# reflex_brainboard_RevG.net
KiCad netlist of a schematic drawn in Altium Designer
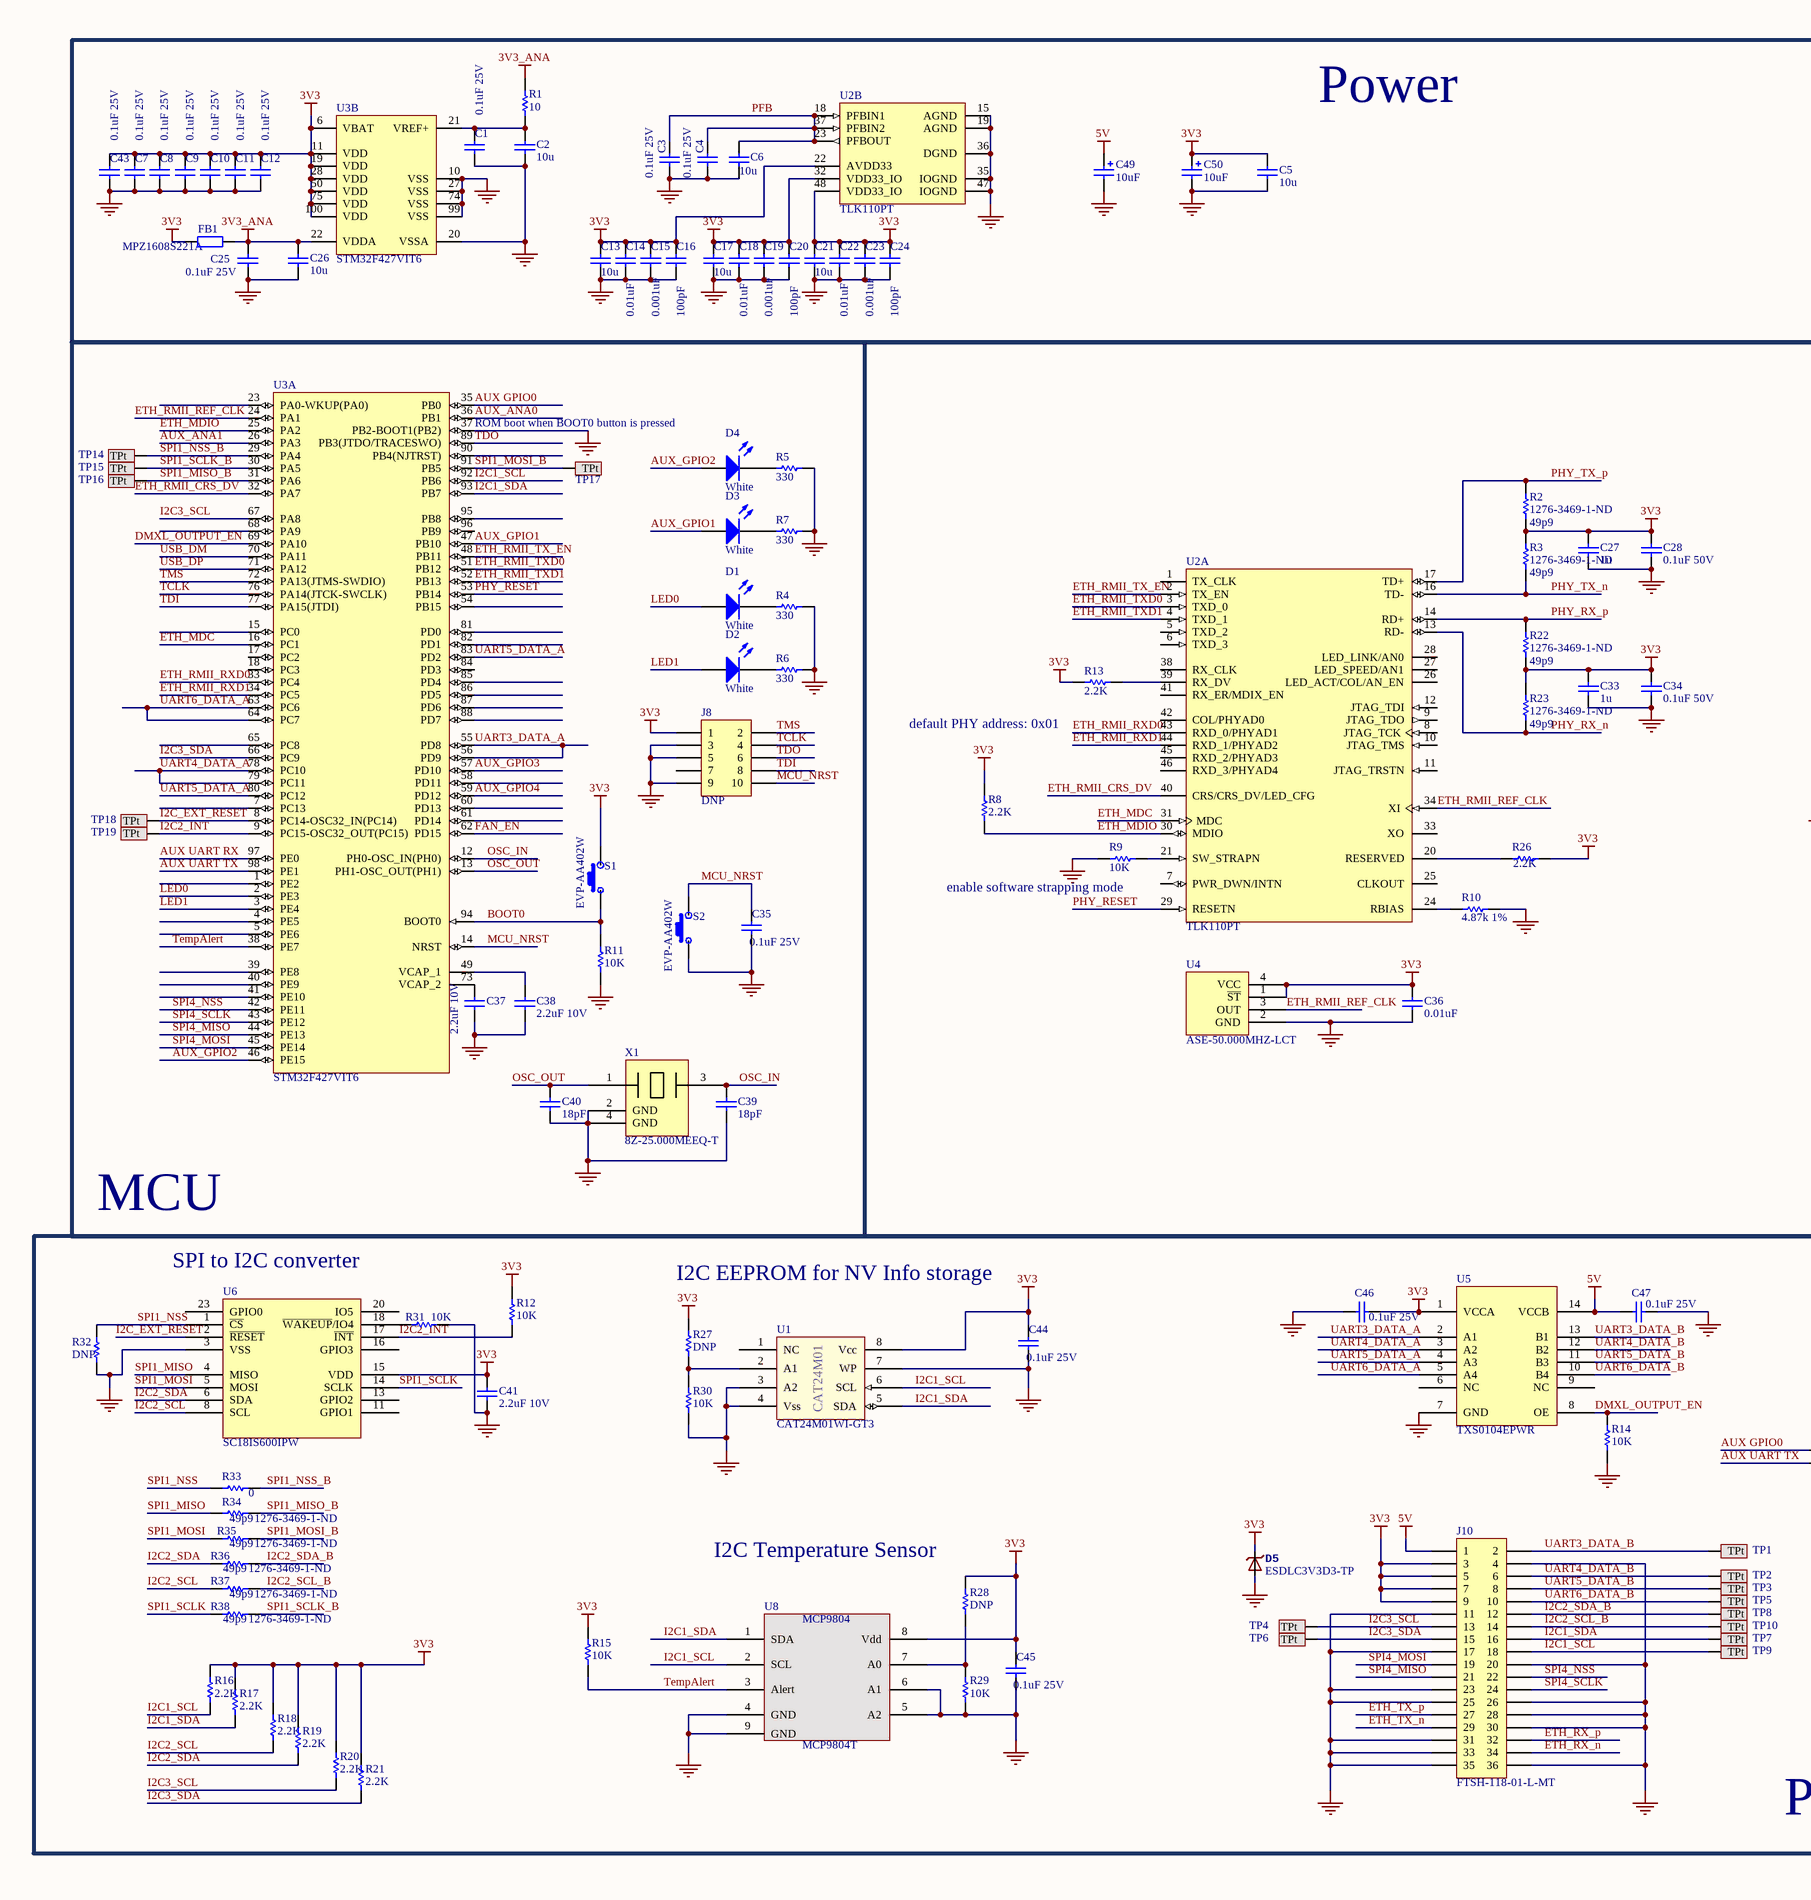
[diagram p0: reflex_brainboard_RevG.SchDoc, left]
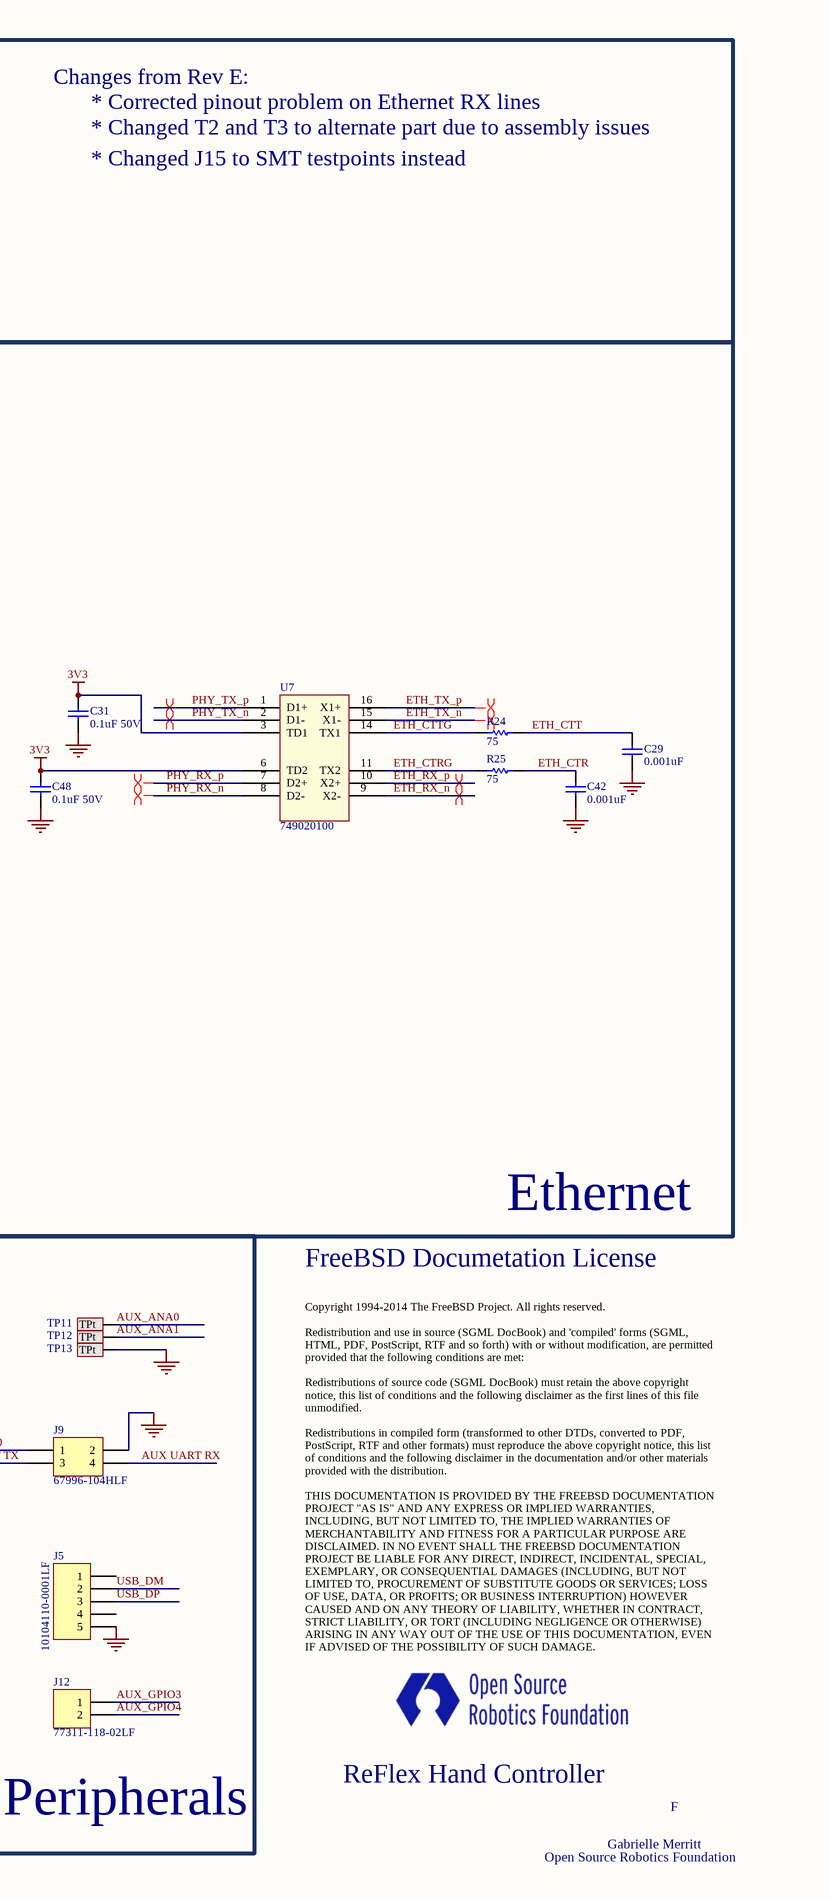
[diagram p1: reflex_brainboard_RevG.SchDoc, right]

(export (version "E")
  (design (tool "Eeschema 10.0.6"))
  (components
    (comp (ref "C1")
      (value "0.1uF 25V")
      (footprint "Generic_0603")
      (description "Capacitor 0.1uF 0603 package")
      (libsource (lib "RHR") (part "Cap_0603_0.1uF_25V"))
    )
    (comp (ref "C2")
      (value "10u")
      (footprint "GENERIC_0603")
      (description "Capacitor")
      (fields
        (field (name "MANUFACTURER") "TDK Corporation")
        (field (name "MANUFACTURER PART NUMBER") "C1608X5R1E106M080AC")
      )
      (libsource (lib "RHR") (part "Cap_0603_10uF"))
    )
    (comp (ref "C3")
      (value "0.1uF 25V")
      (footprint "Generic_0603")
      (description "Capacitor 0.1uF 0603 package")
      (libsource (lib "RHR") (part "Cap_0603_0.1uF_25V"))
    )
    (comp (ref "C4")
      (value "0.1uF 25V")
      (footprint "Generic_0603")
      (description "Capacitor 0.1uF 0603 package")
      (libsource (lib "RHR") (part "Cap_0603_0.1uF_25V"))
    )
    (comp (ref "C5")
      (value "10u")
      (footprint "GENERIC_0603")
      (description "Capacitor")
      (fields
        (field (name "MANUFACTURER") "TDK Corporation")
        (field (name "MANUFACTURER PART NUMBER") "C1608X5R1E106M080AC")
      )
      (libsource (lib "RHR") (part "Cap_0603_10uF"))
    )
    (comp (ref "C6")
      (value "10u")
      (footprint "GENERIC_0603")
      (description "Capacitor")
      (fields
        (field (name "MANUFACTURER") "TDK Corporation")
        (field (name "MANUFACTURER PART NUMBER") "C1608X5R1E106M080AC")
      )
      (libsource (lib "RHR") (part "Cap_0603_10uF"))
    )
    (comp (ref "C7")
      (value "0.1uF 25V")
      (footprint "Generic_0603")
      (description "Capacitor 0.1uF 0603 package")
      (libsource (lib "RHR") (part "Cap_0603_0.1uF_25V"))
    )
    (comp (ref "C8")
      (value "0.1uF 25V")
      (footprint "Generic_0603")
      (description "Capacitor 0.1uF 0603 package")
      (libsource (lib "RHR") (part "Cap_0603_0.1uF_25V"))
    )
    (comp (ref "C9")
      (value "0.1uF 25V")
      (footprint "Generic_0603")
      (description "Capacitor 0.1uF 0603 package")
      (libsource (lib "RHR") (part "Cap_0603_0.1uF_25V"))
    )
    (comp (ref "C10")
      (value "0.1uF 25V")
      (footprint "Generic_0603")
      (description "Capacitor 0.1uF 0603 package")
      (libsource (lib "RHR") (part "Cap_0603_0.1uF_25V"))
    )
    (comp (ref "C11")
      (value "0.1uF 25V")
      (footprint "Generic_0603")
      (description "Capacitor 0.1uF 0603 package")
      (libsource (lib "RHR") (part "Cap_0603_0.1uF_25V"))
    )
    (comp (ref "C12")
      (value "0.1uF 25V")
      (footprint "Generic_0603")
      (description "Capacitor 0.1uF 0603 package")
      (libsource (lib "RHR") (part "Cap_0603_0.1uF_25V"))
    )
    (comp (ref "C13")
      (value "10u")
      (footprint "GENERIC_0603")
      (description "Capacitor")
      (fields
        (field (name "MANUFACTURER") "TDK Corporation")
        (field (name "MANUFACTURER PART NUMBER") "C1608X5R1E106M080AC")
      )
      (libsource (lib "RHR") (part "Cap_0603_10uF"))
    )
    (comp (ref "C14")
      (value "0.01uF")
      (footprint "Generic_0402")
      (description "Capacitor 0.01uF 0402 package")
      (libsource (lib "RHR") (part "Cap_0402_0p01uF"))
    )
    (comp (ref "C15")
      (value "0.001uF")
      (footprint "Generic_0402")
      (description "Capacitor 0.001uF 0402 package")
      (libsource (lib "RHR") (part "Cap_0402_0p001uF"))
    )
    (comp (ref "C16")
      (value "100pF")
      (footprint "Generic_0402")
      (description "Capacitor 100pF 0402 package")
      (libsource (lib "RHR") (part "Cap_0402_100pF"))
    )
    (comp (ref "C17")
      (value "10u")
      (footprint "GENERIC_0603")
      (description "Capacitor")
      (fields
        (field (name "MANUFACTURER") "TDK Corporation")
        (field (name "MANUFACTURER PART NUMBER") "C1608X5R1E106M080AC")
      )
      (libsource (lib "RHR") (part "Cap_0603_10uF"))
    )
    (comp (ref "C18")
      (value "0.01uF")
      (footprint "Generic_0402")
      (description "Capacitor 0.01uF 0402 package")
      (libsource (lib "RHR") (part "Cap_0402_0p01uF"))
    )
    (comp (ref "C19")
      (value "0.001uF")
      (footprint "Generic_0402")
      (description "Capacitor 0.001uF 0402 package")
      (libsource (lib "RHR") (part "Cap_0402_0p001uF"))
    )
    (comp (ref "C20")
      (value "100pF")
      (footprint "Generic_0402")
      (description "Capacitor 100pF 0402 package")
      (libsource (lib "RHR") (part "Cap_0402_100pF"))
    )
    (comp (ref "C21")
      (value "10u")
      (footprint "GENERIC_0603")
      (description "Capacitor")
      (fields
        (field (name "MANUFACTURER") "TDK Corporation")
        (field (name "MANUFACTURER PART NUMBER") "C1608X5R1E106M080AC")
      )
      (libsource (lib "RHR") (part "Cap_0603_10uF"))
    )
    (comp (ref "C22")
      (value "0.01uF")
      (footprint "Generic_0402")
      (description "Capacitor 0.01uF 0402 package")
      (libsource (lib "RHR") (part "Cap_0402_0p01uF"))
    )
    (comp (ref "C23")
      (value "0.001uF")
      (footprint "Generic_0402")
      (description "Capacitor 0.001uF 0402 package")
      (libsource (lib "RHR") (part "Cap_0402_0p001uF"))
    )
    (comp (ref "C24")
      (value "100pF")
      (footprint "Generic_0402")
      (description "Capacitor 100pF 0402 package")
      (libsource (lib "RHR") (part "Cap_0402_100pF"))
    )
    (comp (ref "C25")
      (value "0.1uF 25V")
      (footprint "Generic_0603")
      (description "Capacitor 0.1uF 0603 package")
      (libsource (lib "RHR") (part "Cap_0603_0.1uF_25V"))
    )
    (comp (ref "C26")
      (value "10u")
      (footprint "GENERIC_0603")
      (description "Capacitor")
      (fields
        (field (name "MANUFACTURER") "TDK Corporation")
        (field (name "MANUFACTURER PART NUMBER") "C1608X5R1E106M080AC")
      )
      (libsource (lib "RHR") (part "Cap_0603_10uF"))
    )
    (comp (ref "C27")
      (value "1u")
      (footprint "Generic_0402")
      (description "Capacitor")
      (libsource (lib "RHR") (part "Cap_0402_1uF"))
    )
    (comp (ref "C28")
      (value "0.1uF 50V")
      (footprint "Generic_0402")
      (description "Capacitor 0.1uF 0402 package")
      (fields (field (name "Comment") "0.1uF"))
      (libsource (lib "RHR") (part "Cap_0402_0p1uF_50V"))
    )
    (comp (ref "C29")
      (value "0.001uF")
      (footprint "Generic_0402")
      (description "Capacitor 0.001uF 0402 package")
      (libsource (lib "RHR") (part "Cap_0402_0p001uF"))
    )
    (comp (ref "C31")
      (value "0.1uF 50V")
      (footprint "Generic_0402")
      (description "Capacitor 0.1uF 0402 package")
      (fields (field (name "Comment") "0.1uF"))
      (libsource (lib "RHR") (part "Cap_0402_0p1uF_50V"))
    )
    (comp (ref "C33")
      (value "1u")
      (footprint "Generic_0402")
      (description "Capacitor")
      (libsource (lib "RHR") (part "Cap_0402_1uF"))
    )
    (comp (ref "C34")
      (value "0.1uF 50V")
      (footprint "Generic_0402")
      (description "Capacitor 0.1uF 0402 package")
      (fields (field (name "Comment") "0.1uF"))
      (libsource (lib "RHR") (part "Cap_0402_0p1uF_50V"))
    )
    (comp (ref "C35")
      (value "0.1uF 25V")
      (footprint "Generic_0603")
      (description "Capacitor 0.1uF 0603 package")
      (libsource (lib "RHR") (part "Cap_0603_0.1uF_25V"))
    )
    (comp (ref "C36")
      (value "0.01uF")
      (footprint "Generic_0402")
      (description "Capacitor 0.01uF 0402 package")
      (libsource (lib "RHR") (part "Cap_0402_0p01uF"))
    )
    (comp (ref "C37")
      (value "2.2uF 10V")
      (footprint "Generic_0603")
      (description "Capacitor 2.2uF 0603 package")
      (libsource (lib "RHR") (part "Cap_0603_2p2uF_10V"))
    )
    (comp (ref "C38")
      (value "2.2uF 10V")
      (footprint "Generic_0603")
      (description "Capacitor 2.2uF 0603 package")
      (libsource (lib "RHR") (part "Cap_0603_2p2uF_10V"))
    )
    (comp (ref "C39")
      (value "18pF")
      (footprint "Generic_0402")
      (description "Capacitor 18pF 0402 package")
      (libsource (lib "RHR") (part "Cap_0402_18pF"))
    )
    (comp (ref "C40")
      (value "18pF")
      (footprint "Generic_0402")
      (description "Capacitor 18pF 0402 package")
      (libsource (lib "RHR") (part "Cap_0402_18pF"))
    )
    (comp (ref "C41")
      (value "2.2uF 10V")
      (footprint "Generic_0603")
      (description "Capacitor 2.2uF 0603 package")
      (libsource (lib "RHR") (part "Cap_0603_2p2uF_10V"))
    )
    (comp (ref "C42")
      (value "0.001uF")
      (footprint "Generic_0402")
      (description "Capacitor 0.001uF 0402 package")
      (libsource (lib "RHR") (part "Cap_0402_0p001uF"))
    )
    (comp (ref "C43")
      (value "0.1uF 25V")
      (footprint "Generic_0603")
      (description "Capacitor 0.1uF 0603 package")
      (libsource (lib "RHR") (part "Cap_0603_0.1uF_25V"))
    )
    (comp (ref "C44")
      (value "0.1uF 25V")
      (footprint "Generic_0603")
      (description "Capacitor 0.1uF 0603 package")
      (libsource (lib "RHR") (part "Cap_0603_0.1uF_25V"))
    )
    (comp (ref "C45")
      (value "0.1uF 25V")
      (footprint "Generic_0603")
      (description "Capacitor 0.1uF 0603 package")
      (libsource (lib "RHR") (part "Cap_0603_0.1uF_25V"))
    )
    (comp (ref "C46")
      (value "0.1uF 25V")
      (footprint "Generic_0603")
      (description "Capacitor 0.1uF 0603 package")
      (libsource (lib "RHR") (part "Cap_0603_0.1uF_25V"))
    )
    (comp (ref "C47")
      (value "0.1uF 25V")
      (footprint "Generic_0603")
      (description "Capacitor 0.1uF 0603 package")
      (libsource (lib "RHR") (part "Cap_0603_0.1uF_25V"))
    )
    (comp (ref "C48")
      (value "0.1uF 50V")
      (footprint "Generic_0402")
      (description "Capacitor 0.1uF 0402 package")
      (fields (field (name "Comment") "0.1uF"))
      (libsource (lib "RHR") (part "Cap_0402_0p1uF_50V"))
    )
    (comp (ref "C49")
      (value "10uF")
      (footprint "GENERIC_0805P")
      (description "Polarized Capacitor (Radial)")
      (libsource (lib "RHR") (part "Cap 0805P_10uF"))
    )
    (comp (ref "C50")
      (value "10uF")
      (footprint "GENERIC_0805P")
      (description "Polarized Capacitor (Radial)")
      (libsource (lib "RHR") (part "Cap 0805P_10uF"))
    )
    (comp (ref "D1")
      (value "White")
      (footprint "0402_LED_WHITE")
      (description "Surface mount LEDs")
      (fields (field (name "Comment") "LED White"))
      (libsource (lib "RHR") (part "LED_White_0402"))
    )
    (comp (ref "D2")
      (value "White")
      (footprint "0402_LED_WHITE")
      (description "Surface mount LEDs")
      (fields (field (name "Comment") "LED White"))
      (libsource (lib "RHR") (part "LED_White_0402"))
    )
    (comp (ref "D3")
      (value "White")
      (footprint "0402_LED_WHITE")
      (description "Surface mount LEDs")
      (fields (field (name "Comment") "LED White"))
      (libsource (lib "RHR") (part "LED_White_0402"))
    )
    (comp (ref "D4")
      (value "White")
      (footprint "0402_LED_WHITE")
      (description "Surface mount LEDs")
      (fields (field (name "Comment") "LED White"))
      (libsource (lib "RHR") (part "LED_White_0402"))
    )
    (comp (ref "D5")
      (value "ESDLC3V3D3-TP")
      (footprint "SOD-323")
      (fields (field (name "MANUFACTURER") "Micro Commercial Co"))
      (libsource (lib "RHR") (part "Diode_ESDLC3V3D3-TP"))
    )
    (comp (ref "FB1")
      (value "MPZ1608S221A")
      (footprint "GENERIC_0603")
      (description "Ferrite Bead")
      (fields (field (name "MANUFACTURER") "TDK Corporation"))
      (libsource (lib "RHR") (part "FerriteBead"))
    )
    (comp (ref "J5")
      (value "10104110-0001LF")
      (footprint "FCI-10104110")
      (description "USB Micro Connector")
      (libsource (lib "RHR") (part "Conn_USB_Micro"))
    )
    (comp (ref "J8")
      (value "DNP")
      (footprint "CNCTECH_3220-10-0300-00")
      (description "Header, 5-Pin, Dual row")
      (libsource (lib "RHR") (part "Header 5X2"))
    )
    (comp (ref "J9")
      (value "67996-104HLF")
      (footprint "HDR2X2")
      (description "Header, 2-Pin, Dual row")
      (libsource (lib "RHR") (part "Header 2X2"))
    )
    (comp (ref "J10")
      (value "FTSH-118-01-L-MT")
      (footprint "FTSH-118-01-L-MT")
      (description "Header, 18-Pin, Dual row, Hybrid SMT/Thru")
      (libsource (lib "RHR") (part "Header 18X2 RA MT"))
    )
    (comp (ref "J12")
      (value "77311-118-02LF")
      (footprint "HDR1X2")
      (description "Header, 2-Pin")
      (libsource (lib "RHR") (part "Header 2"))
    )
    (comp (ref "R1")
      (value "10")
      (footprint "Generic_0402")
      (description "Resistor  10 ohm")
      (libsource (lib "RHR") (part "Res_0402_10_1pct"))
    )
    (comp (ref "R2")
      (value "49p9")
      (footprint "Generic_0402")
      (description "Resistor 49.9 ohm")
      (fields
        (field (name "SUPPLIER PART NUMBER 1") "1276-3469-1-ND")
        (field (name "Comment") "Res_0402_49p9_1pct")
      )
      (libsource (lib "RHR") (part "Res_0402_49p9_1pct"))
    )
    (comp (ref "R3")
      (value "49p9")
      (footprint "Generic_0402")
      (description "Resistor 49.9 ohm")
      (fields
        (field (name "SUPPLIER PART NUMBER 1") "1276-3469-1-ND")
        (field (name "Comment") "Res_0402_49p9_1pct")
      )
      (libsource (lib "RHR") (part "Res_0402_49p9_1pct"))
    )
    (comp (ref "R4")
      (value "330")
      (footprint "Generic_0402")
      (description "RES 330 OHM 1/10W 1% 0402 SMD")
      (libsource (lib "RHR") (part "Res_0402_330"))
    )
    (comp (ref "R5")
      (value "330")
      (footprint "Generic_0402")
      (description "RES 330 OHM 1/10W 1% 0402 SMD")
      (libsource (lib "RHR") (part "Res_0402_330"))
    )
    (comp (ref "R6")
      (value "330")
      (footprint "Generic_0402")
      (description "RES 330 OHM 1/10W 1% 0402 SMD")
      (libsource (lib "RHR") (part "Res_0402_330"))
    )
    (comp (ref "R7")
      (value "330")
      (footprint "Generic_0402")
      (description "RES 330 OHM 1/10W 1% 0402 SMD")
      (libsource (lib "RHR") (part "Res_0402_330"))
    )
    (comp (ref "R8")
      (value "2.2K")
      (footprint "Generic_0402")
      (description "Resistor 2.2 Kohm")
      (fields (field (name "Comment") "Res_0402_2.2K"))
      (libsource (lib "RHR") (part "Res_0402_2.2K"))
    )
    (comp (ref "R9")
      (value "10K")
      (footprint "Generic_0402")
      (description "Resistor 10 Kohm")
      (fields (field (name "Comment") "Res_0402_10K_1pct"))
      (libsource (lib "RHR") (part "Res_0402_10K_1pct"))
    )
    (comp (ref "R10")
      (value "4.87k 1%")
      (footprint "Generic_0402")
      (description "75R 0.063W 5% 0402 (1005 Metric)  SMD")
      (libsource (lib "RHR") (part "Res_0402_4p87K_1pct"))
    )
    (comp (ref "R11")
      (value "10K")
      (footprint "Generic_0402")
      (description "Resistor 10 Kohm")
      (fields (field (name "Comment") "Res_0402_10K_1pct"))
      (libsource (lib "RHR") (part "Res_0402_10K_1pct"))
    )
    (comp (ref "R12")
      (value "10K")
      (footprint "Generic_0402")
      (description "Resistor 10 Kohm")
      (fields (field (name "Comment") "Res_0402_10K_1pct"))
      (libsource (lib "RHR") (part "Res_0402_10K_1pct"))
    )
    (comp (ref "R13")
      (value "2.2K")
      (footprint "Generic_0402")
      (description "Resistor 2.2 Kohm")
      (fields (field (name "Comment") "Res_0402_2.2K"))
      (libsource (lib "RHR") (part "Res_0402_2.2K"))
    )
    (comp (ref "R14")
      (value "10K")
      (footprint "Generic_0402")
      (description "Resistor 10 Kohm")
      (fields (field (name "Comment") "Res_0402_10K_1pct"))
      (libsource (lib "RHR") (part "Res_0402_10K_1pct"))
    )
    (comp (ref "R15")
      (value "10K")
      (footprint "Generic_0402")
      (description "Resistor 10 Kohm")
      (fields (field (name "Comment") "Res_0402_10K_1pct"))
      (libsource (lib "RHR") (part "Res_0402_10K_1pct"))
    )
    (comp (ref "R16")
      (value "2.2K")
      (footprint "Generic_0402")
      (description "Resistor 2.2 Kohm")
      (fields (field (name "Comment") "Res_0402_2.2K"))
      (libsource (lib "RHR") (part "Res_0402_2.2K"))
    )
    (comp (ref "R17")
      (value "2.2K")
      (footprint "Generic_0402")
      (description "Resistor 2.2 Kohm")
      (fields (field (name "Comment") "Res_0402_2.2K"))
      (libsource (lib "RHR") (part "Res_0402_2.2K"))
    )
    (comp (ref "R18")
      (value "2.2K")
      (footprint "Generic_0402")
      (description "Resistor 2.2 Kohm")
      (fields (field (name "Comment") "Res_0402_2.2K"))
      (libsource (lib "RHR") (part "Res_0402_2.2K"))
    )
    (comp (ref "R19")
      (value "2.2K")
      (footprint "Generic_0402")
      (description "Resistor 2.2 Kohm")
      (fields (field (name "Comment") "Res_0402_2.2K"))
      (libsource (lib "RHR") (part "Res_0402_2.2K"))
    )
    (comp (ref "R20")
      (value "2.2K")
      (footprint "Generic_0402")
      (description "Resistor 2.2 Kohm")
      (fields (field (name "Comment") "Res_0402_2.2K"))
      (libsource (lib "RHR") (part "Res_0402_2.2K"))
    )
    (comp (ref "R21")
      (value "2.2K")
      (footprint "Generic_0402")
      (description "Resistor 2.2 Kohm")
      (fields (field (name "Comment") "Res_0402_2.2K"))
      (libsource (lib "RHR") (part "Res_0402_2.2K"))
    )
    (comp (ref "R22")
      (value "49p9")
      (footprint "Generic_0402")
      (description "Resistor 49.9 ohm")
      (fields
        (field (name "SUPPLIER PART NUMBER 1") "1276-3469-1-ND")
        (field (name "Comment") "Res_0402_49p9_1pct")
      )
      (libsource (lib "RHR") (part "Res_0402_49p9_1pct"))
    )
    (comp (ref "R23")
      (value "49p9")
      (footprint "Generic_0402")
      (description "Resistor 49.9 ohm")
      (fields
        (field (name "SUPPLIER PART NUMBER 1") "1276-3469-1-ND")
        (field (name "Comment") "Res_0402_49p9_1pct")
      )
      (libsource (lib "RHR") (part "Res_0402_49p9_1pct"))
    )
    (comp (ref "R24")
      (value "75")
      (footprint "Generic_0402")
      (description "75R 0.063W 5% 0402 (1005 Metric)  SMD")
      (libsource (lib "RHR") (part "Res_0402_75_1pct"))
    )
    (comp (ref "R25")
      (value "75")
      (footprint "Generic_0402")
      (description "75R 0.063W 5% 0402 (1005 Metric)  SMD")
      (libsource (lib "RHR") (part "Res_0402_75_1pct"))
    )
    (comp (ref "R26")
      (value "2.2K")
      (footprint "Generic_0402")
      (description "Resistor 2.2 Kohm")
      (fields (field (name "Comment") "Res_0402_2.2K"))
      (libsource (lib "RHR") (part "Res_0402_2.2K"))
    )
    (comp (ref "R27")
      (value "DNP")
      (footprint "Generic_0402")
      (description "Resistor 0402 DNP")
      (fields (field (name "Comment") "Res_0402_DNP"))
      (libsource (lib "RHR") (part "Res_0402_DNP"))
    )
    (comp (ref "R28")
      (value "DNP")
      (footprint "Generic_0402")
      (description "Resistor 0402 DNP")
      (fields (field (name "Comment") "Res_0402_DNP"))
      (libsource (lib "RHR") (part "Res_0402_DNP"))
    )
    (comp (ref "R29")
      (value "10K")
      (footprint "Generic_0402")
      (description "Resistor 10 Kohm")
      (fields (field (name "Comment") "Res_0402_10K_1pct"))
      (libsource (lib "RHR") (part "Res_0402_10K_1pct"))
    )
    (comp (ref "R30")
      (value "10K")
      (footprint "Generic_0402")
      (description "Resistor 10 Kohm")
      (fields (field (name "Comment") "Res_0402_10K_1pct"))
      (libsource (lib "RHR") (part "Res_0402_10K_1pct"))
    )
    (comp (ref "R31")
      (value "10K")
      (footprint "Generic_0402")
      (description "Resistor 10 Kohm")
      (fields (field (name "Comment") "Res_0402_10K_1pct"))
      (libsource (lib "RHR") (part "Res_0402_10K_1pct"))
    )
    (comp (ref "R32")
      (value "DNP")
      (footprint "Generic_0402")
      (description "Resistor 0402 DNP")
      (fields (field (name "Comment") "Res_0402_DNP"))
      (libsource (lib "RHR") (part "Res_0402_DNP"))
    )
    (comp (ref "R33")
      (value "0")
      (footprint "GENERIC_0402")
      (description "RES SMD 0 OHM JUMPER 1/10W 0402")
      (fields (field (name "Comment") "Res_0402_0"))
      (libsource (lib "RHR") (part "Res_0402_0"))
    )
    (comp (ref "R34")
      (value "49p9")
      (footprint "Generic_0402")
      (description "Resistor 49.9 ohm")
      (fields
        (field (name "SUPPLIER PART NUMBER 1") "1276-3469-1-ND")
        (field (name "Comment") "Res_0402_49p9_1pct")
      )
      (libsource (lib "RHR") (part "Res_0402_49p9_1pct"))
    )
    (comp (ref "R35")
      (value "49p9")
      (footprint "Generic_0402")
      (description "Resistor 49.9 ohm")
      (fields
        (field (name "SUPPLIER PART NUMBER 1") "1276-3469-1-ND")
        (field (name "Comment") "Res_0402_49p9_1pct")
      )
      (libsource (lib "RHR") (part "Res_0402_49p9_1pct"))
    )
    (comp (ref "R36")
      (value "49p9")
      (footprint "Generic_0402")
      (description "Resistor 49.9 ohm")
      (fields
        (field (name "SUPPLIER PART NUMBER 1") "1276-3469-1-ND")
        (field (name "Comment") "Res_0402_49p9_1pct")
      )
      (libsource (lib "RHR") (part "Res_0402_49p9_1pct"))
    )
    (comp (ref "R37")
      (value "49p9")
      (footprint "Generic_0402")
      (description "Resistor 49.9 ohm")
      (fields
        (field (name "SUPPLIER PART NUMBER 1") "1276-3469-1-ND")
        (field (name "Comment") "Res_0402_49p9_1pct")
      )
      (libsource (lib "RHR") (part "Res_0402_49p9_1pct"))
    )
    (comp (ref "R38")
      (value "49p9")
      (footprint "Generic_0402")
      (description "Resistor 49.9 ohm")
      (fields
        (field (name "SUPPLIER PART NUMBER 1") "1276-3469-1-ND")
        (field (name "Comment") "Res_0402_49p9_1pct")
      )
      (libsource (lib "RHR") (part "Res_0402_49p9_1pct"))
    )
    (comp (ref "S1")
      (value "EVP-AA402W")
      (footprint "EVPAA402_switch")
      (description "Momentary Push button, NO")
      (libsource (lib "RHR") (part "Pushbutton_EVP-AA402W"))
    )
    (comp (ref "S2")
      (value "EVP-AA402W")
      (footprint "EVPAA402_switch")
      (description "Momentary Push button, NO")
      (libsource (lib "RHR") (part "Pushbutton_EVP-AA402W"))
    )
    (comp (ref "TP1")
      (value "SMT Pad")
      (footprint "TP_PAD_20mil")
      (description "SMT pad for test")
      (libsource (lib "") (part "TP_SMT_20mil_1"))
    )
    (comp (ref "TP2")
      (value "SMT Pad")
      (footprint "TP_PAD_20mil")
      (description "SMT pad for test")
      (libsource (lib "") (part "TP_SMT_20mil_1"))
    )
    (comp (ref "TP3")
      (value "SMT Pad")
      (footprint "TP_PAD_20mil")
      (description "SMT pad for test")
      (libsource (lib "") (part "TP_SMT_20mil_1"))
    )
    (comp (ref "TP4")
      (value "SMT Pad")
      (footprint "TP_PAD_20mil")
      (description "SMT pad for test")
      (libsource (lib "RHR") (part "TP_SMT_20mil"))
    )
    (comp (ref "TP5")
      (value "SMT Pad")
      (footprint "TP_PAD_20mil")
      (description "SMT pad for test")
      (libsource (lib "") (part "TP_SMT_20mil_1"))
    )
    (comp (ref "TP6")
      (value "SMT Pad")
      (footprint "TP_PAD_20mil")
      (description "SMT pad for test")
      (libsource (lib "RHR") (part "TP_SMT_20mil"))
    )
    (comp (ref "TP7")
      (value "SMT Pad")
      (footprint "TP_PAD_20mil")
      (description "SMT pad for test")
      (libsource (lib "") (part "TP_SMT_20mil_1"))
    )
    (comp (ref "TP8")
      (value "SMT Pad")
      (footprint "TP_PAD_20mil")
      (description "SMT pad for test")
      (libsource (lib "") (part "TP_SMT_20mil_1"))
    )
    (comp (ref "TP9")
      (value "SMT Pad")
      (footprint "TP_PAD_20mil")
      (description "SMT pad for test")
      (libsource (lib "") (part "TP_SMT_20mil_1"))
    )
    (comp (ref "TP10")
      (value "SMT Pad")
      (footprint "TP_PAD_20mil")
      (description "SMT pad for test")
      (libsource (lib "") (part "TP_SMT_20mil_1"))
    )
    (comp (ref "TP11")
      (value "SMT Pad")
      (footprint "TP_PAD_20mil")
      (description "SMT pad for test")
      (libsource (lib "RHR") (part "TP_SMT_20mil"))
    )
    (comp (ref "TP12")
      (value "SMT Pad")
      (footprint "TP_PAD_20mil")
      (description "SMT pad for test")
      (libsource (lib "RHR") (part "TP_SMT_20mil"))
    )
    (comp (ref "TP13")
      (value "SMT Pad")
      (footprint "TP_PAD_20mil")
      (description "SMT pad for test")
      (libsource (lib "RHR") (part "TP_SMT_20mil"))
    )
    (comp (ref "TP14")
      (value "SMT Pad")
      (footprint "TP_PAD_20mil")
      (description "SMT pad for test")
      (libsource (lib "RHR") (part "TP_SMT_20mil"))
    )
    (comp (ref "TP15")
      (value "SMT Pad")
      (footprint "TP_PAD_20mil")
      (description "SMT pad for test")
      (libsource (lib "RHR") (part "TP_SMT_20mil"))
    )
    (comp (ref "TP16")
      (value "SMT Pad")
      (footprint "TP_PAD_20mil")
      (description "SMT pad for test")
      (libsource (lib "RHR") (part "TP_SMT_20mil"))
    )
    (comp (ref "TP17")
      (value "SMT Pad")
      (footprint "TP_PAD_20mil")
      (description "SMT pad for test")
      (libsource (lib "") (part "TP_SMT_20mil_1"))
    )
    (comp (ref "TP18")
      (value "SMT Pad")
      (footprint "TP_PAD_20mil")
      (description "SMT pad for test")
      (libsource (lib "RHR") (part "TP_SMT_20mil"))
    )
    (comp (ref "TP19")
      (value "SMT Pad")
      (footprint "TP_PAD_20mil")
      (description "SMT pad for test")
      (libsource (lib "RHR") (part "TP_SMT_20mil"))
    )
    (comp (ref "U1")
      (value "CAT24M01WI-GT3")
      (footprint "SOIC8")
      (description "I2C EEPROM 1Mbit")
      (libsource (lib "RHR") (part "IC_EEPROM_I2C_1Mbit"))
    )
    (comp (ref "U2")
      (value "TLK110PT")
      (footprint "TI-PT48_M")
      (libsource (lib "RHR") (part "IC_TLK110PT_EthernetPhy"))
    )
    (comp (ref "U3")
      (value "STM32F427VIT6")
      (footprint "STM-LQFP100_N")
      (fields (field (name "MANUFACTURER") "STMicroelectronics"))
      (libsource (lib "RHR") (part "MC-ARM-STM32F4X7-SQ100"))
    )
    (comp (ref "U4")
      (value "ASE-50.000MHZ-LCT")
      (footprint "OSCILLATOR_3.2x2.5")
      (libsource (lib "RHR") (part "oscillator_3.2x2.5"))
    )
    (comp (ref "U5")
      (value "TXS0104EPWR")
      (footprint "TXS0104EPWR")
      (description "Level Shifter")
      (libsource (lib "RHR") (part "IC_LevelShifter_TXS0104EPWR"))
    )
    (comp (ref "U6")
      (value "SC18IS600IPW")
      (footprint "HVQFN24")
      (description "SPI to I2C Converter")
      (libsource (lib "RHR") (part "IC_SPI_to_I2C_SC18IS600IPW"))
    )
    (comp (ref "U7")
      (value "749020100")
      (footprint "Wurth749020100")
      (description "Ethernet Magnetics Wurth 749020100")
      (libsource (lib "RHR") (part "IC_EthernetMagnetics"))
    )
    (comp (ref "U8")
      (value "MCP9804T")
      (footprint "Temp_MCP9804T")
      (description "I2C Temp Sensor MCP9804T-E/MC")
      (libsource (lib "RHR") (part "IC_Temp_Sensor_MCP9804_I2C"))
    )
    (comp (ref "X1")
      (value "8Z-25.000MEEQ-T")
      (footprint "CRYSTAL_2_2.5")
      (libsource (lib "RHR") (part "CRYSTAL"))
    )
  )
  (nets
    (net (code "1") (name "/AUX GPIO0") (class "Default")
      (node (ref "J9") (pin "1") (pinfunction "1_1") (pintype "passive"))
      (node (ref "U3") (pin "35") (pinfunction "PB0_35") (pintype "bidirectional"))
    )
    (net (code "2") (name "/AUX UART RX") (class "Default")
      (node (ref "J9") (pin "4") (pinfunction "4_4") (pintype "passive"))
      (node (ref "U3") (pin "97") (pinfunction "PE0_97") (pintype "bidirectional"))
    )
    (net (code "3") (name "/AUX UART TX") (class "Default")
      (node (ref "J9") (pin "3") (pinfunction "3_3") (pintype "passive"))
      (node (ref "U3") (pin "98") (pinfunction "PE1_98") (pintype "bidirectional"))
    )
    (net (code "4") (name "/AUX_ANA0") (class "Default")
      (node (ref "TP11") (pin "1") (pinfunction "TPt_1") (pintype "passive"))
      (node (ref "U3") (pin "36") (pinfunction "PB1_36") (pintype "bidirectional"))
    )
    (net (code "5") (name "/AUX_ANA1") (class "Default")
      (node (ref "TP12") (pin "1") (pinfunction "TPt_1") (pintype "passive"))
      (node (ref "U3") (pin "26") (pinfunction "PA3_26") (pintype "bidirectional"))
    )
    (net (code "6") (name "/AUX_GPIO1") (class "Default")
      (node (ref "D3") (pin "1") (pinfunction "A_1") (pintype "passive"))
      (node (ref "U3") (pin "47") (pinfunction "PB10_47") (pintype "bidirectional"))
    )
    (net (code "7") (name "/AUX_GPIO2") (class "Default")
      (node (ref "D4") (pin "1") (pinfunction "A_1") (pintype "passive"))
      (node (ref "U3") (pin "46") (pinfunction "PE15_46") (pintype "bidirectional"))
    )
    (net (code "8") (name "/AUX_GPIO3") (class "Default")
      (node (ref "J12") (pin "1") (pinfunction "1_1") (pintype "passive"))
      (node (ref "U3") (pin "57") (pinfunction "PD10_57") (pintype "bidirectional"))
    )
    (net (code "9") (name "/AUX_GPIO4") (class "Default")
      (node (ref "J12") (pin "2") (pinfunction "2_2") (pintype "passive"))
      (node (ref "U3") (pin "59") (pinfunction "PD12_59") (pintype "bidirectional"))
    )
    (net (code "10") (name "/BOOT0") (class "Default")
      (node (ref "R11") (pin "2") (pinfunction "2_2") (pintype "passive"))
      (node (ref "S1") (pin "2") (pinfunction "2_2") (pintype "power_in"))
      (node (ref "U3") (pin "94") (pinfunction "BOOT0_94") (pintype "input"))
    )
    (net (code "11") (name "/DMXL_OUTPUT_EN") (class "Default")
      (node (ref "R14") (pin "2") (pinfunction "2_2") (pintype "passive"))
      (node (ref "U3") (pin "69") (pinfunction "PA10_69") (pintype "bidirectional"))
      (node (ref "U5") (pin "8") (pinfunction "OE_8") (pintype "power_in"))
    )
    (net (code "12") (name "/ETH_CTR") (class "Default")
      (node (ref "C42") (pin "2") (pinfunction "2_2") (pintype "passive"))
      (node (ref "R25") (pin "2") (pinfunction "2_2") (pintype "passive"))
    )
    (net (code "13") (name "/ETH_CTRG") (class "Default")
      (node (ref "R25") (pin "1") (pinfunction "1_1") (pintype "passive"))
      (node (ref "U7") (pin "11") (pinfunction "TX2_11") (pintype "passive"))
    )
    (net (code "14") (name "/ETH_CTT") (class "Default")
      (node (ref "C29") (pin "2") (pinfunction "2_2") (pintype "passive"))
      (node (ref "R24") (pin "2") (pinfunction "2_2") (pintype "passive"))
    )
    (net (code "15") (name "/ETH_CTTG") (class "Default")
      (node (ref "R24") (pin "1") (pinfunction "1_1") (pintype "passive"))
      (node (ref "U7") (pin "14") (pinfunction "TX1_14") (pintype "passive"))
    )
    (net (code "16") (name "/ETH_MDC") (class "Default")
      (node (ref "U2") (pin "31") (pinfunction "MDC_31") (pintype "input"))
      (node (ref "U3") (pin "16") (pinfunction "PC1_16") (pintype "bidirectional"))
    )
    (net (code "17") (name "/ETH_MDIO") (class "Default")
      (node (ref "R8") (pin "2") (pinfunction "2_2") (pintype "passive"))
      (node (ref "U2") (pin "30") (pinfunction "MDIO_30") (pintype "bidirectional"))
      (node (ref "U3") (pin "25") (pinfunction "PA2_25") (pintype "bidirectional"))
    )
    (net (code "18") (name "/ETH_RMII_CRS_DV") (class "Default")
      (node (ref "U2") (pin "40") (pinfunction "CRS/CRS_DV/LED_CFG_40") (pintype "tri_state"))
      (node (ref "U3") (pin "32") (pinfunction "PA7_32") (pintype "bidirectional"))
    )
    (net (code "19") (name "/ETH_RMII_REF_CLK") (class "Default")
      (node (ref "U2") (pin "34") (pinfunction "XI_34") (pintype "input"))
      (node (ref "U3") (pin "24") (pinfunction "PA1_24") (pintype "bidirectional"))
      (node (ref "U4") (pin "3") (pinfunction "OUT_3") (pintype "passive"))
    )
    (net (code "20") (name "/ETH_RMII_RXD0") (class "Default")
      (node (ref "U2") (pin "43") (pinfunction "RXD_0/PHYAD1_43") (pintype "tri_state"))
      (node (ref "U3") (pin "33") (pinfunction "PC4_33") (pintype "bidirectional"))
    )
    (net (code "21") (name "/ETH_RMII_RXD1") (class "Default")
      (node (ref "U2") (pin "44") (pinfunction "RXD_1/PHYAD2_44") (pintype "tri_state"))
      (node (ref "U3") (pin "34") (pinfunction "PC5_34") (pintype "bidirectional"))
    )
    (net (code "22") (name "/ETH_RMII_TXD0") (class "Default")
      (node (ref "U2") (pin "3") (pinfunction "TXD_0_3") (pintype "input"))
      (node (ref "U3") (pin "51") (pinfunction "PB12_51") (pintype "bidirectional"))
    )
    (net (code "23") (name "/ETH_RMII_TXD1") (class "Default")
      (node (ref "U2") (pin "4") (pinfunction "TXD_1_4") (pintype "input"))
      (node (ref "U3") (pin "52") (pinfunction "PB13_52") (pintype "bidirectional"))
    )
    (net (code "24") (name "/ETH_RMII_TX_EN") (class "Default")
      (node (ref "U2") (pin "2") (pinfunction "TX_EN_2") (pintype "input"))
      (node (ref "U3") (pin "48") (pinfunction "PB11_48") (pintype "bidirectional"))
    )
    (net (code "25") (name "/ETH_RX_n") (class "Default")
      (node (ref "J10") (pin "34") (pinfunction "34_34") (pintype "passive"))
      (node (ref "U7") (pin "9") (pinfunction "X2-_9") (pintype "passive"))
    )
    (net (code "26") (name "/ETH_RX_p") (class "Default")
      (node (ref "J10") (pin "32") (pinfunction "32_32") (pintype "passive"))
      (node (ref "U7") (pin "10") (pinfunction "X2+_10") (pintype "passive"))
    )
    (net (code "27") (name "/ETH_TX_n") (class "Default")
      (node (ref "J10") (pin "29") (pinfunction "29_29") (pintype "passive"))
      (node (ref "U7") (pin "15") (pinfunction "X1-_15") (pintype "passive"))
    )
    (net (code "28") (name "/ETH_TX_p") (class "Default")
      (node (ref "J10") (pin "27") (pinfunction "27_27") (pintype "passive"))
      (node (ref "U7") (pin "16") (pinfunction "X1+_16") (pintype "passive"))
    )
    (net (code "29") (name "/FAN_EN") (class "Default")
      (node (ref "U3") (pin "62") (pinfunction "PD15_62") (pintype "bidirectional"))
    )
    (net (code "30") (name "/I2C1_SCL") (class "Default")
      (node (ref "J10") (pin "18") (pinfunction "18_18") (pintype "passive"))
      (node (ref "R16") (pin "1") (pinfunction "1_1") (pintype "passive"))
      (node (ref "TP9") (pin "1") (pinfunction "TPt_1") (pintype "passive"))
      (node (ref "U1") (pin "6") (pinfunction "SCL_6") (pintype "input"))
      (node (ref "U3") (pin "92") (pinfunction "PB6_92") (pintype "bidirectional"))
      (node (ref "U8") (pin "2") (pinfunction "SCL_2") (pintype "passive"))
    )
    (net (code "31") (name "/I2C1_SDA") (class "Default")
      (node (ref "J10") (pin "16") (pinfunction "16_16") (pintype "passive"))
      (node (ref "R17") (pin "1") (pinfunction "1_1") (pintype "passive"))
      (node (ref "TP7") (pin "1") (pinfunction "TPt_1") (pintype "passive"))
      (node (ref "U1") (pin "5") (pinfunction "SDA_5") (pintype "bidirectional"))
      (node (ref "U3") (pin "93") (pinfunction "PB7_93") (pintype "bidirectional"))
      (node (ref "U8") (pin "1") (pinfunction "SDA_1") (pintype "passive"))
    )
    (net (code "32") (name "/I2C2_INT") (class "Default")
      (node (ref "R12") (pin "1") (pinfunction "1_1") (pintype "passive"))
      (node (ref "TP19") (pin "1") (pinfunction "TPt_1") (pintype "passive"))
      (node (ref "U3") (pin "9") (pinfunction "PC15-OSC32_OUT(PC15)_9") (pintype "bidirectional"))
      (node (ref "U6") (pin "17") (pinfunction "~{INT}_17") (pintype "power_in"))
    )
    (net (code "33") (name "/I2C2_SCL") (class "Default")
      (node (ref "R18") (pin "1") (pinfunction "1_1") (pintype "passive"))
      (node (ref "R37") (pin "2") (pinfunction "2_2") (pintype "passive"))
      (node (ref "U6") (pin "8") (pinfunction "SCL_8") (pintype "power_in"))
    )
    (net (code "34") (name "/I2C2_SCL_B") (class "Default")
      (node (ref "J10") (pin "14") (pinfunction "14_14") (pintype "passive"))
      (node (ref "R37") (pin "1") (pinfunction "1_1") (pintype "passive"))
      (node (ref "TP10") (pin "1") (pinfunction "TPt_1") (pintype "passive"))
    )
    (net (code "35") (name "/I2C2_SDA") (class "Default")
      (node (ref "R19") (pin "1") (pinfunction "1_1") (pintype "passive"))
      (node (ref "R36") (pin "2") (pinfunction "2_2") (pintype "passive"))
      (node (ref "U6") (pin "6") (pinfunction "SDA_6") (pintype "power_in"))
    )
    (net (code "36") (name "/I2C2_SDA_B") (class "Default")
      (node (ref "J10") (pin "12") (pinfunction "12_12") (pintype "passive"))
      (node (ref "R36") (pin "1") (pinfunction "1_1") (pintype "passive"))
      (node (ref "TP8") (pin "1") (pinfunction "TPt_1") (pintype "passive"))
    )
    (net (code "37") (name "/I2C3_SCL") (class "Default")
      (node (ref "J10") (pin "13") (pinfunction "13_13") (pintype "passive"))
      (node (ref "R20") (pin "1") (pinfunction "1_1") (pintype "passive"))
      (node (ref "TP4") (pin "1") (pinfunction "TPt_1") (pintype "passive"))
      (node (ref "U3") (pin "67") (pinfunction "PA8_67") (pintype "bidirectional"))
    )
    (net (code "38") (name "/I2C3_SDA") (class "Default")
      (node (ref "J10") (pin "15") (pinfunction "15_15") (pintype "passive"))
      (node (ref "R21") (pin "1") (pinfunction "1_1") (pintype "passive"))
      (node (ref "TP6") (pin "1") (pinfunction "TPt_1") (pintype "passive"))
      (node (ref "U3") (pin "66") (pinfunction "PC9_66") (pintype "bidirectional"))
    )
    (net (code "39") (name "/I2C_EXT_~{RESE}T") (class "Default")
      (node (ref "TP18") (pin "1") (pinfunction "TPt_1") (pintype "passive"))
      (node (ref "U3") (pin "8") (pinfunction "PC14-OSC32_IN(PC14)_8") (pintype "bidirectional"))
      (node (ref "U6") (pin "2") (pinfunction "~{RESET}_2") (pintype "power_in"))
    )
    (net (code "40") (name "/LED0") (class "Default")
      (node (ref "D1") (pin "1") (pinfunction "A_1") (pintype "passive"))
      (node (ref "U3") (pin "2") (pinfunction "PE3_2") (pintype "bidirectional"))
    )
    (net (code "41") (name "/LED1") (class "Default")
      (node (ref "D2") (pin "1") (pinfunction "A_1") (pintype "passive"))
      (node (ref "U3") (pin "3") (pinfunction "PE4_3") (pintype "bidirectional"))
    )
    (net (code "42") (name "/MCU_NRST") (class "Default")
      (node (ref "C35") (pin "2") (pinfunction "2_2") (pintype "passive"))
      (node (ref "J8") (pin "10") (pinfunction "10_10") (pintype "passive"))
      (node (ref "S2") (pin "1") (pinfunction "1_1") (pintype "power_in"))
      (node (ref "U3") (pin "14") (pinfunction "NRST_14") (pintype "bidirectional"))
    )
    (net (code "43") (name "/OSC_IN") (class "Default")
      (node (ref "C39") (pin "1") (pinfunction "1_1") (pintype "passive"))
      (node (ref "U3") (pin "12") (pinfunction "PH0-OSC_IN(PH0)_12") (pintype "bidirectional"))
      (node (ref "X1") (pin "3") (pinfunction "3_3") (pintype "passive"))
    )
    (net (code "44") (name "/OSC_OUT") (class "Default")
      (node (ref "C40") (pin "1") (pinfunction "1_1") (pintype "passive"))
      (node (ref "U3") (pin "13") (pinfunction "PH1-OSC_OUT(PH1)_13") (pintype "bidirectional"))
      (node (ref "X1") (pin "1") (pinfunction "1_1") (pintype "passive"))
    )
    (net (code "45") (name "/PFB") (class "Default")
      (node (ref "C3") (pin "1") (pinfunction "1_1") (pintype "passive"))
      (node (ref "C4") (pin "2") (pinfunction "2_2") (pintype "passive"))
      (node (ref "C6") (pin "2") (pinfunction "2_2") (pintype "passive"))
      (node (ref "U2") (pin "18") (pinfunction "PFBIN1_18") (pintype "input"))
      (node (ref "U2") (pin "23") (pinfunction "PFBOUT_23") (pintype "output"))
      (node (ref "U2") (pin "37") (pinfunction "PFBIN2_37") (pintype "input"))
    )
    (net (code "46") (name "/PHY_RESET") (class "Default")
      (node (ref "U2") (pin "29") (pinfunction "RESETN_29") (pintype "input"))
      (node (ref "U3") (pin "53") (pinfunction "PB14_53") (pintype "bidirectional"))
    )
    (net (code "47") (name "/PHY_RX_n") (class "Default")
      (node (ref "R23") (pin "1") (pinfunction "1_1") (pintype "passive"))
      (node (ref "U2") (pin "13") (pinfunction "RD-_13") (pintype "bidirectional"))
      (node (ref "U7") (pin "8") (pinfunction "D2-_8") (pintype "passive"))
    )
    (net (code "48") (name "/PHY_RX_p") (class "Default")
      (node (ref "R22") (pin "2") (pinfunction "2_2") (pintype "passive"))
      (node (ref "U2") (pin "14") (pinfunction "RD+_14") (pintype "bidirectional"))
      (node (ref "U7") (pin "7") (pinfunction "D2+_7") (pintype "passive"))
    )
    (net (code "49") (name "/PHY_TX_n") (class "Default")
      (node (ref "R3") (pin "1") (pinfunction "1_1") (pintype "passive"))
      (node (ref "U2") (pin "16") (pinfunction "TD-_16") (pintype "bidirectional"))
      (node (ref "U7") (pin "2") (pinfunction "D1-_2") (pintype "passive"))
    )
    (net (code "50") (name "/PHY_TX_p") (class "Default")
      (node (ref "R2") (pin "1") (pinfunction "1_1") (pintype "passive"))
      (node (ref "U2") (pin "17") (pinfunction "TD+_17") (pintype "bidirectional"))
      (node (ref "U7") (pin "1") (pinfunction "D1+_1") (pintype "passive"))
    )
    (net (code "51") (name "/SPI1_MISO") (class "Default")
      (node (ref "R34") (pin "2") (pinfunction "2_2") (pintype "passive"))
      (node (ref "U6") (pin "4") (pinfunction "MISO_4") (pintype "power_in"))
    )
    (net (code "52") (name "/SPI1_MISO_B") (class "Default")
      (node (ref "R34") (pin "1") (pinfunction "1_1") (pintype "passive"))
      (node (ref "TP16") (pin "1") (pinfunction "TPt_1") (pintype "passive"))
      (node (ref "U3") (pin "31") (pinfunction "PA6_31") (pintype "bidirectional"))
    )
    (net (code "53") (name "/SPI1_MOSI") (class "Default")
      (node (ref "R35") (pin "2") (pinfunction "2_2") (pintype "passive"))
      (node (ref "U6") (pin "5") (pinfunction "MOSI_5") (pintype "power_in"))
    )
    (net (code "54") (name "/SPI1_MOSI_B") (class "Default")
      (node (ref "R35") (pin "1") (pinfunction "1_1") (pintype "passive"))
      (node (ref "TP17") (pin "1") (pinfunction "TPt_1") (pintype "passive"))
      (node (ref "U3") (pin "91") (pinfunction "PB5_91") (pintype "bidirectional"))
    )
    (net (code "55") (name "/SPI1_NSS") (class "Default")
      (node (ref "R32") (pin "1") (pinfunction "1_1") (pintype "passive"))
      (node (ref "R33") (pin "2") (pinfunction "2_2") (pintype "passive"))
      (node (ref "U6") (pin "1") (pinfunction "~{CS}_1") (pintype "power_in"))
    )
    (net (code "56") (name "/SPI1_NSS_B") (class "Default")
      (node (ref "R33") (pin "1") (pinfunction "1_1") (pintype "passive"))
      (node (ref "TP14") (pin "1") (pinfunction "TPt_1") (pintype "passive"))
      (node (ref "U3") (pin "29") (pinfunction "PA4_29") (pintype "bidirectional"))
    )
    (net (code "57") (name "/SPI1_SCLK") (class "Default")
      (node (ref "R38") (pin "2") (pinfunction "2_2") (pintype "passive"))
      (node (ref "U6") (pin "14") (pinfunction "SCLK_14") (pintype "power_in"))
    )
    (net (code "58") (name "/SPI1_SCLK_B") (class "Default")
      (node (ref "R38") (pin "1") (pinfunction "1_1") (pintype "passive"))
      (node (ref "TP15") (pin "1") (pinfunction "TPt_1") (pintype "passive"))
      (node (ref "U3") (pin "30") (pinfunction "PA5_30") (pintype "bidirectional"))
    )
    (net (code "59") (name "/SPI4_MISO") (class "Default")
      (node (ref "J10") (pin "21") (pinfunction "21_21") (pintype "passive"))
      (node (ref "U3") (pin "44") (pinfunction "PE13_44") (pintype "bidirectional"))
    )
    (net (code "60") (name "/SPI4_MOSI") (class "Default")
      (node (ref "J10") (pin "19") (pinfunction "19_19") (pintype "passive"))
      (node (ref "U3") (pin "45") (pinfunction "PE14_45") (pintype "bidirectional"))
    )
    (net (code "61") (name "/SPI4_NSS") (class "Default")
      (node (ref "J10") (pin "22") (pinfunction "22_22") (pintype "passive"))
      (node (ref "U3") (pin "42") (pinfunction "PE11_42") (pintype "bidirectional"))
    )
    (net (code "62") (name "/SPI4_SCLK") (class "Default")
      (node (ref "J10") (pin "24") (pinfunction "24_24") (pintype "passive"))
      (node (ref "U3") (pin "43") (pinfunction "PE12_43") (pintype "bidirectional"))
    )
    (net (code "63") (name "/TCLK") (class "Default")
      (node (ref "J8") (pin "4") (pinfunction "4_4") (pintype "passive"))
      (node (ref "U3") (pin "76") (pinfunction "PA14(JTCK-SWCLK)_76") (pintype "bidirectional"))
    )
    (net (code "64") (name "/TDI") (class "Default")
      (node (ref "J8") (pin "8") (pinfunction "8_8") (pintype "passive"))
      (node (ref "U3") (pin "77") (pinfunction "PA15(JTDI)_77") (pintype "bidirectional"))
    )
    (net (code "65") (name "/TDO") (class "Default")
      (node (ref "J8") (pin "6") (pinfunction "6_6") (pintype "passive"))
      (node (ref "U3") (pin "89") (pinfunction "PB3(JTDO/TRACESWO)_89") (pintype "bidirectional"))
    )
    (net (code "66") (name "/TMS") (class "Default")
      (node (ref "J8") (pin "2") (pinfunction "2_2") (pintype "passive"))
      (node (ref "U3") (pin "72") (pinfunction "PA13(JTMS-SWDIO)_72") (pintype "bidirectional"))
    )
    (net (code "67") (name "/TempAlert") (class "Default")
      (node (ref "R15") (pin "1") (pinfunction "1_1") (pintype "passive"))
      (node (ref "U3") (pin "38") (pinfunction "PE7_38") (pintype "bidirectional"))
      (node (ref "U8") (pin "3") (pinfunction "Alert_3") (pintype "passive"))
    )
    (net (code "68") (name "/UART3_DATA_A") (class "Default")
      (node (ref "U3") (pin "55") (pinfunction "PD8_55") (pintype "bidirectional"))
      (node (ref "U3") (pin "56") (pinfunction "PD9_56") (pintype "bidirectional"))
      (node (ref "U5") (pin "2") (pinfunction "A1_2") (pintype "power_in"))
    )
    (net (code "69") (name "/UART3_DATA_B") (class "Default")
      (node (ref "J10") (pin "2") (pinfunction "2_2") (pintype "passive"))
      (node (ref "TP1") (pin "1") (pinfunction "TPt_1") (pintype "passive"))
      (node (ref "U5") (pin "13") (pinfunction "B1_13") (pintype "power_in"))
    )
    (net (code "70") (name "/UART4_DATA_A") (class "Default")
      (node (ref "U3") (pin "78") (pinfunction "PC10_78") (pintype "bidirectional"))
      (node (ref "U3") (pin "79") (pinfunction "PC11_79") (pintype "bidirectional"))
      (node (ref "U5") (pin "3") (pinfunction "A2_3") (pintype "power_in"))
    )
    (net (code "71") (name "/UART4_DATA_B") (class "Default")
      (node (ref "J10") (pin "6") (pinfunction "6_6") (pintype "passive"))
      (node (ref "TP2") (pin "1") (pinfunction "TPt_1") (pintype "passive"))
      (node (ref "U5") (pin "12") (pinfunction "B2_12") (pintype "power_in"))
    )
    (net (code "72") (name "/UART5_DATA_A") (class "Default")
      (node (ref "U3") (pin "80") (pinfunction "PC12_80") (pintype "bidirectional"))
      (node (ref "U3") (pin "83") (pinfunction "PD2_83") (pintype "bidirectional"))
      (node (ref "U5") (pin "4") (pinfunction "A3_4") (pintype "power_in"))
    )
    (net (code "73") (name "/UART5_DATA_B") (class "Default")
      (node (ref "J10") (pin "8") (pinfunction "8_8") (pintype "passive"))
      (node (ref "TP3") (pin "1") (pinfunction "TPt_1") (pintype "passive"))
      (node (ref "U5") (pin "11") (pinfunction "B3_11") (pintype "power_in"))
    )
    (net (code "74") (name "/UART6_DATA_A") (class "Default")
      (node (ref "U3") (pin "63") (pinfunction "PC6_63") (pintype "bidirectional"))
      (node (ref "U3") (pin "64") (pinfunction "PC7_64") (pintype "bidirectional"))
      (node (ref "U5") (pin "5") (pinfunction "A4_5") (pintype "power_in"))
    )
    (net (code "75") (name "/UART6_DATA_B") (class "Default")
      (node (ref "J10") (pin "10") (pinfunction "10_10") (pintype "passive"))
      (node (ref "TP5") (pin "1") (pinfunction "TPt_1") (pintype "passive"))
      (node (ref "U5") (pin "10") (pinfunction "B4_10") (pintype "power_in"))
    )
    (net (code "76") (name "/USB_DM") (class "Default")
      (node (ref "J5") (pin "2") (pinfunction "2_2") (pintype "passive"))
      (node (ref "U3") (pin "70") (pinfunction "PA11_70") (pintype "bidirectional"))
    )
    (net (code "77") (name "/USB_DP") (class "Default")
      (node (ref "J5") (pin "3") (pinfunction "3_3") (pintype "passive"))
      (node (ref "U3") (pin "71") (pinfunction "PA12_71") (pintype "bidirectional"))
    )
    (net (code "78") (name "3V3") (class "Default")
      (node (ref "C10") (pin "2") (pinfunction "2_2") (pintype "passive"))
      (node (ref "C11") (pin "2") (pinfunction "2_2") (pintype "passive"))
      (node (ref "C12") (pin "2") (pinfunction "2_2") (pintype "passive"))
      (node (ref "C13") (pin "2") (pinfunction "2_2") (pintype "passive"))
      (node (ref "C14") (pin "2") (pinfunction "2_2") (pintype "passive"))
      (node (ref "C15") (pin "2") (pinfunction "2_2") (pintype "passive"))
      (node (ref "C16") (pin "2") (pinfunction "2_2") (pintype "passive"))
      (node (ref "C17") (pin "2") (pinfunction "2_2") (pintype "passive"))
      (node (ref "C18") (pin "2") (pinfunction "2_2") (pintype "passive"))
      (node (ref "C19") (pin "2") (pinfunction "2_2") (pintype "passive"))
      (node (ref "C20") (pin "2") (pinfunction "2_2") (pintype "passive"))
      (node (ref "C21") (pin "2") (pinfunction "2_2") (pintype "passive"))
      (node (ref "C22") (pin "2") (pinfunction "2_2") (pintype "passive"))
      (node (ref "C23") (pin "2") (pinfunction "2_2") (pintype "passive"))
      (node (ref "C24") (pin "2") (pinfunction "2_2") (pintype "passive"))
      (node (ref "C27") (pin "2") (pinfunction "2_2") (pintype "passive"))
      (node (ref "C28") (pin "2") (pinfunction "2_2") (pintype "passive"))
      (node (ref "C31") (pin "2") (pinfunction "2_2") (pintype "passive"))
      (node (ref "C33") (pin "2") (pinfunction "2_2") (pintype "passive"))
      (node (ref "C34") (pin "2") (pinfunction "2_2") (pintype "passive"))
      (node (ref "C36") (pin "2") (pinfunction "2_2") (pintype "passive"))
      (node (ref "C41") (pin "2") (pinfunction "2_2") (pintype "passive"))
      (node (ref "C43") (pin "2") (pinfunction "2_2") (pintype "passive"))
      (node (ref "C44") (pin "2") (pinfunction "2_2") (pintype "passive"))
      (node (ref "C45") (pin "2") (pinfunction "2_2") (pintype "passive"))
      (node (ref "C46") (pin "1") (pinfunction "1_1") (pintype "passive"))
      (node (ref "C48") (pin "2") (pinfunction "2_2") (pintype "passive"))
      (node (ref "C5") (pin "2") (pinfunction "2_2") (pintype "passive"))
      (node (ref "C50") (pin "1") (pinfunction "1_1") (pintype "passive"))
      (node (ref "C7") (pin "2") (pinfunction "2_2") (pintype "passive"))
      (node (ref "C8") (pin "2") (pinfunction "2_2") (pintype "passive"))
      (node (ref "C9") (pin "2") (pinfunction "2_2") (pintype "passive"))
      (node (ref "D5") (pin "1") (pinfunction "A_1") (pintype "passive"))
      (node (ref "FB1") (pin "1") (pinfunction "1_1") (pintype "passive"))
      (node (ref "J10") (pin "3") (pinfunction "3_3") (pintype "passive"))
      (node (ref "J10") (pin "5") (pinfunction "5_5") (pintype "passive"))
      (node (ref "J10") (pin "7") (pinfunction "7_7") (pintype "passive"))
      (node (ref "J10") (pin "9") (pinfunction "9_9") (pintype "passive"))
      (node (ref "J8") (pin "1") (pinfunction "1_1") (pintype "passive"))
      (node (ref "R12") (pin "2") (pinfunction "2_2") (pintype "passive"))
      (node (ref "R13") (pin "2") (pinfunction "2_2") (pintype "passive"))
      (node (ref "R15") (pin "2") (pinfunction "2_2") (pintype "passive"))
      (node (ref "R16") (pin "2") (pinfunction "2_2") (pintype "passive"))
      (node (ref "R17") (pin "2") (pinfunction "2_2") (pintype "passive"))
      (node (ref "R18") (pin "2") (pinfunction "2_2") (pintype "passive"))
      (node (ref "R19") (pin "2") (pinfunction "2_2") (pintype "passive"))
      (node (ref "R2") (pin "2") (pinfunction "2_2") (pintype "passive"))
      (node (ref "R20") (pin "2") (pinfunction "2_2") (pintype "passive"))
      (node (ref "R21") (pin "2") (pinfunction "2_2") (pintype "passive"))
      (node (ref "R22") (pin "1") (pinfunction "1_1") (pintype "passive"))
      (node (ref "R23") (pin "2") (pinfunction "2_2") (pintype "passive"))
      (node (ref "R26") (pin "2") (pinfunction "2_2") (pintype "passive"))
      (node (ref "R27") (pin "2") (pinfunction "2_2") (pintype "passive"))
      (node (ref "R28") (pin "2") (pinfunction "2_2") (pintype "passive"))
      (node (ref "R3") (pin "2") (pinfunction "2_2") (pintype "passive"))
      (node (ref "R8") (pin "1") (pinfunction "1_1") (pintype "passive"))
      (node (ref "S1") (pin "1") (pinfunction "1_1") (pintype "power_in"))
      (node (ref "U1") (pin "8") (pinfunction "Vcc_8") (pintype "power_in"))
      (node (ref "U2") (pin "22") (pinfunction "AVDD33_22") (pintype "power_in"))
      (node (ref "U2") (pin "32") (pinfunction "VDD33_IO_32") (pintype "power_in"))
      (node (ref "U2") (pin "48") (pinfunction "VDD33_IO_48") (pintype "power_in"))
      (node (ref "U3") (pin "100") (pinfunction "VDD_100") (pintype "power_in"))
      (node (ref "U3") (pin "11") (pinfunction "VDD_11") (pintype "power_in"))
      (node (ref "U3") (pin "19") (pinfunction "VDD_19") (pintype "power_in"))
      (node (ref "U3") (pin "28") (pinfunction "VDD_28") (pintype "power_in"))
      (node (ref "U3") (pin "50") (pinfunction "VDD_50") (pintype "power_in"))
      (node (ref "U3") (pin "6") (pinfunction "VBAT_6") (pintype "power_in"))
      (node (ref "U3") (pin "75") (pinfunction "VDD_75") (pintype "power_in"))
      (node (ref "U4") (pin "1") (pinfunction "ST_1") (pintype "passive"))
      (node (ref "U4") (pin "4") (pinfunction "VCC_4") (pintype "passive"))
      (node (ref "U5") (pin "1") (pinfunction "VCCA_1") (pintype "power_in"))
      (node (ref "U6") (pin "15") (pinfunction "VDD_15") (pintype "power_in"))
      (node (ref "U7") (pin "3") (pinfunction "TD1_3") (pintype "passive"))
      (node (ref "U7") (pin "6") (pinfunction "TD2_6") (pintype "passive"))
      (node (ref "U8") (pin "8") (pinfunction "Vdd_8") (pintype "passive"))
    )
    (net (code "79") (name "3V3_ANA") (class "Default")
      (node (ref "C25") (pin "2") (pinfunction "2_2") (pintype "passive"))
      (node (ref "C26") (pin "2") (pinfunction "2_2") (pintype "passive"))
      (node (ref "FB1") (pin "2") (pinfunction "2_2") (pintype "passive"))
      (node (ref "R1") (pin "2") (pinfunction "2_2") (pintype "passive"))
      (node (ref "U3") (pin "22") (pinfunction "VDDA_22") (pintype "power_in"))
    )
    (net (code "80") (name "5V") (class "Default")
      (node (ref "C47") (pin "2") (pinfunction "2_2") (pintype "passive"))
      (node (ref "C49") (pin "1") (pinfunction "1_1") (pintype "passive"))
      (node (ref "J10") (pin "1") (pinfunction "1_1") (pintype "passive"))
      (node (ref "U5") (pin "14") (pinfunction "VCCB_14") (pintype "power_in"))
    )
    (net (code "81") (name "GND") (class "Default")
      (node (ref "C1") (pin "1") (pinfunction "1_1") (pintype "passive"))
      (node (ref "C10") (pin "1") (pinfunction "1_1") (pintype "passive"))
      (node (ref "C11") (pin "1") (pinfunction "1_1") (pintype "passive"))
      (node (ref "C12") (pin "1") (pinfunction "1_1") (pintype "passive"))
      (node (ref "C13") (pin "1") (pinfunction "1_1") (pintype "passive"))
      (node (ref "C14") (pin "1") (pinfunction "1_1") (pintype "passive"))
      (node (ref "C15") (pin "1") (pinfunction "1_1") (pintype "passive"))
      (node (ref "C16") (pin "1") (pinfunction "1_1") (pintype "passive"))
      (node (ref "C17") (pin "1") (pinfunction "1_1") (pintype "passive"))
      (node (ref "C18") (pin "1") (pinfunction "1_1") (pintype "passive"))
      (node (ref "C19") (pin "1") (pinfunction "1_1") (pintype "passive"))
      (node (ref "C2") (pin "1") (pinfunction "1_1") (pintype "passive"))
      (node (ref "C20") (pin "1") (pinfunction "1_1") (pintype "passive"))
      (node (ref "C21") (pin "1") (pinfunction "1_1") (pintype "passive"))
      (node (ref "C22") (pin "1") (pinfunction "1_1") (pintype "passive"))
      (node (ref "C23") (pin "1") (pinfunction "1_1") (pintype "passive"))
      (node (ref "C24") (pin "1") (pinfunction "1_1") (pintype "passive"))
      (node (ref "C25") (pin "1") (pinfunction "1_1") (pintype "passive"))
      (node (ref "C26") (pin "1") (pinfunction "1_1") (pintype "passive"))
      (node (ref "C27") (pin "1") (pinfunction "1_1") (pintype "passive"))
      (node (ref "C28") (pin "1") (pinfunction "1_1") (pintype "passive"))
      (node (ref "C29") (pin "1") (pinfunction "1_1") (pintype "passive"))
      (node (ref "C3") (pin "2") (pinfunction "2_2") (pintype "passive"))
      (node (ref "C31") (pin "1") (pinfunction "1_1") (pintype "passive"))
      (node (ref "C33") (pin "1") (pinfunction "1_1") (pintype "passive"))
      (node (ref "C34") (pin "1") (pinfunction "1_1") (pintype "passive"))
      (node (ref "C35") (pin "1") (pinfunction "1_1") (pintype "passive"))
      (node (ref "C36") (pin "1") (pinfunction "1_1") (pintype "passive"))
      (node (ref "C37") (pin "1") (pinfunction "1_1") (pintype "passive"))
      (node (ref "C38") (pin "1") (pinfunction "1_1") (pintype "passive"))
      (node (ref "C39") (pin "2") (pinfunction "2_2") (pintype "passive"))
      (node (ref "C4") (pin "1") (pinfunction "1_1") (pintype "passive"))
      (node (ref "C40") (pin "2") (pinfunction "2_2") (pintype "passive"))
      (node (ref "C41") (pin "1") (pinfunction "1_1") (pintype "passive"))
      (node (ref "C42") (pin "1") (pinfunction "1_1") (pintype "passive"))
      (node (ref "C43") (pin "1") (pinfunction "1_1") (pintype "passive"))
      (node (ref "C44") (pin "1") (pinfunction "1_1") (pintype "passive"))
      (node (ref "C45") (pin "1") (pinfunction "1_1") (pintype "passive"))
      (node (ref "C46") (pin "2") (pinfunction "2_2") (pintype "passive"))
      (node (ref "C47") (pin "1") (pinfunction "1_1") (pintype "passive"))
      (node (ref "C48") (pin "1") (pinfunction "1_1") (pintype "passive"))
      (node (ref "C49") (pin "2") (pinfunction "2_2") (pintype "passive"))
      (node (ref "C5") (pin "1") (pinfunction "1_1") (pintype "passive"))
      (node (ref "C50") (pin "2") (pinfunction "2_2") (pintype "passive"))
      (node (ref "C6") (pin "1") (pinfunction "1_1") (pintype "passive"))
      (node (ref "C7") (pin "1") (pinfunction "1_1") (pintype "passive"))
      (node (ref "C8") (pin "1") (pinfunction "1_1") (pintype "passive"))
      (node (ref "C9") (pin "1") (pinfunction "1_1") (pintype "passive"))
      (node (ref "D5") (pin "2") (pinfunction "C_2") (pintype "passive"))
      (node (ref "J10") (pin "11") (pinfunction "11_11") (pintype "passive"))
      (node (ref "J10") (pin "17") (pinfunction "17_17") (pintype "passive"))
      (node (ref "J10") (pin "20") (pinfunction "20_20") (pintype "passive"))
      (node (ref "J10") (pin "23") (pinfunction "23_23") (pintype "passive"))
      (node (ref "J10") (pin "25") (pinfunction "25_25") (pintype "passive"))
      (node (ref "J10") (pin "26") (pinfunction "26_26") (pintype "passive"))
      (node (ref "J10") (pin "28") (pinfunction "28_28") (pintype "passive"))
      (node (ref "J10") (pin "30") (pinfunction "30_30") (pintype "passive"))
      (node (ref "J10") (pin "31") (pinfunction "31_31") (pintype "passive"))
      (node (ref "J10") (pin "33") (pinfunction "33_33") (pintype "passive"))
      (node (ref "J10") (pin "35") (pinfunction "35_35") (pintype "passive"))
      (node (ref "J10") (pin "36") (pinfunction "36_36") (pintype "passive"))
      (node (ref "J10") (pin "4") (pinfunction "4_4") (pintype "passive"))
      (node (ref "J5") (pin "5") (pinfunction "5_5") (pintype "passive"))
      (node (ref "J8") (pin "3") (pinfunction "3_3") (pintype "passive"))
      (node (ref "J8") (pin "5") (pinfunction "5_5") (pintype "passive"))
      (node (ref "J8") (pin "9") (pinfunction "9_9") (pintype "passive"))
      (node (ref "J9") (pin "2") (pinfunction "2_2") (pintype "passive"))
      (node (ref "R10") (pin "1") (pinfunction "1_1") (pintype "passive"))
      (node (ref "R11") (pin "1") (pinfunction "1_1") (pintype "passive"))
      (node (ref "R14") (pin "1") (pinfunction "1_1") (pintype "passive"))
      (node (ref "R29") (pin "1") (pinfunction "1_1") (pintype "passive"))
      (node (ref "R30") (pin "1") (pinfunction "1_1") (pintype "passive"))
      (node (ref "R31") (pin "1") (pinfunction "1_1") (pintype "passive"))
      (node (ref "R32") (pin "2") (pinfunction "2_2") (pintype "passive"))
      (node (ref "R4") (pin "1") (pinfunction "1_1") (pintype "passive"))
      (node (ref "R5") (pin "1") (pinfunction "1_1") (pintype "passive"))
      (node (ref "R6") (pin "1") (pinfunction "1_1") (pintype "passive"))
      (node (ref "R7") (pin "1") (pinfunction "1_1") (pintype "passive"))
      (node (ref "R9") (pin "1") (pinfunction "1_1") (pintype "passive"))
      (node (ref "S2") (pin "2") (pinfunction "2_2") (pintype "power_in"))
      (node (ref "TP13") (pin "1") (pinfunction "TPt_1") (pintype "passive"))
      (node (ref "U1") (pin "3") (pinfunction "A2_3") (pintype "passive"))
      (node (ref "U1") (pin "4") (pinfunction "Vss_4") (pintype "power_in"))
      (node (ref "U1") (pin "7") (pinfunction "WP_7") (pintype "passive"))
      (node (ref "U2") (pin "15") (pinfunction "AGND_15") (pintype "power_in"))
      (node (ref "U2") (pin "19") (pinfunction "AGND_19") (pintype "power_in"))
      (node (ref "U2") (pin "35") (pinfunction "IOGND_35") (pintype "power_in"))
      (node (ref "U2") (pin "36") (pinfunction "DGND_36") (pintype "power_in"))
      (node (ref "U2") (pin "47") (pinfunction "IOGND_47") (pintype "power_in"))
      (node (ref "U3") (pin "10") (pinfunction "VSS_10") (pintype "power_in"))
      (node (ref "U3") (pin "20") (pinfunction "VSSA_20") (pintype "power_in"))
      (node (ref "U3") (pin "27") (pinfunction "VSS_27") (pintype "power_in"))
      (node (ref "U3") (pin "37") (pinfunction "PB2-BOOT1(PB2)_37") (pintype "bidirectional"))
      (node (ref "U3") (pin "74") (pinfunction "VSS_74") (pintype "power_in"))
      (node (ref "U3") (pin "99") (pinfunction "VSS_99") (pintype "power_in"))
      (node (ref "U4") (pin "2") (pinfunction "GND_2") (pintype "passive"))
      (node (ref "U5") (pin "7") (pinfunction "GND_7") (pintype "power_in"))
      (node (ref "U6") (pin "3") (pinfunction "VSS_3") (pintype "power_in"))
      (node (ref "U8") (pin "4") (pinfunction "GND_4") (pintype "passive"))
      (node (ref "U8") (pin "5") (pinfunction "A2_5") (pintype "passive"))
      (node (ref "U8") (pin "6") (pinfunction "A1_6") (pintype "passive"))
      (node (ref "U8") (pin "9") (pinfunction "GND_9") (pintype "passive"))
      (node (ref "X1") (pin "2") (pinfunction "GND_2") (pintype "passive"))
      (node (ref "X1") (pin "4") (pinfunction "GND_4") (pintype "passive"))
    )
    (net (code "82") (name "Net-(D1-K)") (class "Default")
      (node (ref "D1") (pin "2") (pinfunction "K_2") (pintype "passive"))
      (node (ref "R4") (pin "2") (pinfunction "2_2") (pintype "passive"))
    )
    (net (code "83") (name "Net-(D2-K)") (class "Default")
      (node (ref "D2") (pin "2") (pinfunction "K_2") (pintype "passive"))
      (node (ref "R6") (pin "2") (pinfunction "2_2") (pintype "passive"))
    )
    (net (code "84") (name "Net-(D3-K)") (class "Default")
      (node (ref "D3") (pin "2") (pinfunction "K_2") (pintype "passive"))
      (node (ref "R7") (pin "2") (pinfunction "2_2") (pintype "passive"))
    )
    (net (code "85") (name "Net-(D4-K)") (class "Default")
      (node (ref "D4") (pin "2") (pinfunction "K_2") (pintype "passive"))
      (node (ref "R5") (pin "2") (pinfunction "2_2") (pintype "passive"))
    )
    (net (code "86") (name "Net-(U1-A1)") (class "Default")
      (node (ref "R27") (pin "1") (pinfunction "1_1") (pintype "passive"))
      (node (ref "R30") (pin "2") (pinfunction "2_2") (pintype "passive"))
      (node (ref "U1") (pin "2") (pinfunction "A1_2") (pintype "passive"))
    )
    (net (code "87") (name "Net-(U2A-RBIAS)") (class "Default")
      (node (ref "R10") (pin "2") (pinfunction "2_2") (pintype "passive"))
      (node (ref "U2") (pin "24") (pinfunction "RBIAS_24") (pintype "passive"))
    )
    (net (code "88") (name "Net-(U2A-RESERVED)") (class "Default")
      (node (ref "R26") (pin "1") (pinfunction "1_1") (pintype "passive"))
      (node (ref "U2") (pin "20") (pinfunction "RESERVED_20") (pintype "passive"))
    )
    (net (code "89") (name "Net-(U2A-RX_DV)") (class "Default")
      (node (ref "R13") (pin "1") (pinfunction "1_1") (pintype "passive"))
      (node (ref "U2") (pin "39") (pinfunction "RX_DV_39") (pintype "tri_state"))
    )
    (net (code "90") (name "Net-(U2A-SW_STRAPN)") (class "Default")
      (node (ref "R9") (pin "2") (pinfunction "2_2") (pintype "passive"))
      (node (ref "U2") (pin "21") (pinfunction "SW_STRAPN_21") (pintype "input"))
    )
    (net (code "91") (name "Net-(U3A-VCAP_1)") (class "Default")
      (node (ref "C38") (pin "2") (pinfunction "2_2") (pintype "passive"))
      (node (ref "U3") (pin "49") (pinfunction "VCAP_1_49") (pintype "power_in"))
    )
    (net (code "92") (name "Net-(U3A-VCAP_2)") (class "Default")
      (node (ref "C37") (pin "2") (pinfunction "2_2") (pintype "passive"))
      (node (ref "U3") (pin "73") (pinfunction "VCAP_2_73") (pintype "power_in"))
    )
    (net (code "93") (name "Net-(U3B-VREF+)") (class "Default")
      (node (ref "C1") (pin "2") (pinfunction "2_2") (pintype "passive"))
      (node (ref "C2") (pin "2") (pinfunction "2_2") (pintype "passive"))
      (node (ref "R1") (pin "1") (pinfunction "1_1") (pintype "passive"))
      (node (ref "U3") (pin "21") (pinfunction "VREF+_21") (pintype "power_in"))
    )
    (net (code "94") (name "Net-(U6-~{WAKEUP}{slash}IO4)") (class "Default")
      (node (ref "R31") (pin "2") (pinfunction "2_2") (pintype "passive"))
      (node (ref "U6") (pin "18") (pinfunction "~{WAKEUP}/IO4_18") (pintype "power_in"))
    )
    (net (code "95") (name "Net-(U8-A0)") (class "Default")
      (node (ref "R28") (pin "1") (pinfunction "1_1") (pintype "passive"))
      (node (ref "R29") (pin "2") (pinfunction "2_2") (pintype "passive"))
      (node (ref "U8") (pin "7") (pinfunction "A0_7") (pintype "passive"))
    )
    (net (code "96") (name "unconnected-(J5-Pad1)") (class "Default")
      (node (ref "J5") (pin "1") (pinfunction "1_1") (pintype "passive"))
    )
    (net (code "97") (name "unconnected-(J5-Pad4)") (class "Default")
      (node (ref "J5") (pin "4") (pinfunction "4_4") (pintype "passive"))
    )
    (net (code "98") (name "unconnected-(J8-Pad7)") (class "Default")
      (node (ref "J8") (pin "7") (pinfunction "7_7") (pintype "passive"))
    )
    (net (code "99") (name "unconnected-(U1-NC-Pad1)") (class "Default")
      (node (ref "U1") (pin "1") (pinfunction "NC_1") (pintype "passive"))
    )
    (net (code "100") (name "unconnected-(U2A-CLKOUT-Pad25)") (class "Default")
      (node (ref "U2") (pin "25") (pinfunction "CLKOUT_25") (pintype "tri_state"))
    )
    (net (code "101") (name "unconnected-(U2A-COL{slash}PHYAD0-Pad42)") (class "Default")
      (node (ref "U2") (pin "42") (pinfunction "COL/PHYAD0_42") (pintype "tri_state"))
    )
    (net (code "102") (name "unconnected-(U2A-JTAG_TCK-Pad8)") (class "Default")
      (node (ref "U2") (pin "8") (pinfunction "JTAG_TCK_8") (pintype "input"))
    )
    (net (code "103") (name "unconnected-(U2A-JTAG_TDI-Pad12)") (class "Default")
      (node (ref "U2") (pin "12") (pinfunction "JTAG_TDI_12") (pintype "input"))
    )
    (net (code "104") (name "unconnected-(U2A-JTAG_TDO-Pad9)") (class "Default")
      (node (ref "U2") (pin "9") (pinfunction "JTAG_TDO_9") (pintype "output"))
    )
    (net (code "105") (name "unconnected-(U2A-JTAG_TMS-Pad10)") (class "Default")
      (node (ref "U2") (pin "10") (pinfunction "JTAG_TMS_10") (pintype "input"))
    )
    (net (code "106") (name "unconnected-(U2A-JTAG_TRSTN-Pad11)") (class "Default")
      (node (ref "U2") (pin "11") (pinfunction "JTAG_TRSTN_11") (pintype "input"))
    )
    (net (code "107") (name "unconnected-(U2A-LED_ACT{slash}COL{slash}AN_EN-Pad26)") (class "Default")
      (node (ref "U2") (pin "26") (pinfunction "LED_ACT/COL/AN_EN_26") (pintype "tri_state"))
    )
    (net (code "108") (name "unconnected-(U2A-LED_LINK{slash}AN0-Pad28)") (class "Default")
      (node (ref "U2") (pin "28") (pinfunction "LED_LINK/AN0_28") (pintype "tri_state"))
    )
    (net (code "109") (name "unconnected-(U2A-LED_SPEED{slash}AN1-Pad27)") (class "Default")
      (node (ref "U2") (pin "27") (pinfunction "LED_SPEED/AN1_27") (pintype "tri_state"))
    )
    (net (code "110") (name "unconnected-(U2A-PWR_DWN{slash}INTN-Pad7)") (class "Default")
      (node (ref "U2") (pin "7") (pinfunction "PWR_DWN/INTN_7") (pintype "bidirectional"))
    )
    (net (code "111") (name "unconnected-(U2A-RXD_2{slash}PHYAD3-Pad45)") (class "Default")
      (node (ref "U2") (pin "45") (pinfunction "RXD_2/PHYAD3_45") (pintype "tri_state"))
    )
    (net (code "112") (name "unconnected-(U2A-RXD_3{slash}PHYAD4-Pad46)") (class "Default")
      (node (ref "U2") (pin "46") (pinfunction "RXD_3/PHYAD4_46") (pintype "tri_state"))
    )
    (net (code "113") (name "unconnected-(U2A-RX_CLK-Pad38)") (class "Default")
      (node (ref "U2") (pin "38") (pinfunction "RX_CLK_38") (pintype "tri_state"))
    )
    (net (code "114") (name "unconnected-(U2A-RX_ER{slash}MDIX_EN-Pad41)") (class "Default")
      (node (ref "U2") (pin "41") (pinfunction "RX_ER/MDIX_EN_41") (pintype "tri_state"))
    )
    (net (code "115") (name "unconnected-(U2A-TXD_2-Pad5)") (class "Default")
      (node (ref "U2") (pin "5") (pinfunction "TXD_2_5") (pintype "input"))
    )
    (net (code "116") (name "unconnected-(U2A-TXD_3-Pad6)") (class "Default")
      (node (ref "U2") (pin "6") (pinfunction "TXD_3_6") (pintype "input"))
    )
    (net (code "117") (name "unconnected-(U2A-TX_CLK-Pad1)") (class "Default")
      (node (ref "U2") (pin "1") (pinfunction "TX_CLK_1") (pintype "tri_state"))
    )
    (net (code "118") (name "unconnected-(U2A-XO-Pad33)") (class "Default")
      (node (ref "U2") (pin "33") (pinfunction "XO_33") (pintype "passive"))
    )
    (net (code "119") (name "unconnected-(U3A-PA0-WKUP(PA0)-Pad23)") (class "Default")
      (node (ref "U3") (pin "23") (pinfunction "PA0-WKUP(PA0)_23") (pintype "bidirectional"))
    )
    (net (code "120") (name "unconnected-(U3A-PA9-Pad68)") (class "Default")
      (node (ref "U3") (pin "68") (pinfunction "PA9_68") (pintype "bidirectional"))
    )
    (net (code "121") (name "unconnected-(U3A-PB4(NJTRST)-Pad90)") (class "Default")
      (node (ref "U3") (pin "90") (pinfunction "PB4(NJTRST)_90") (pintype "bidirectional"))
    )
    (net (code "122") (name "unconnected-(U3A-PB8-Pad95)") (class "Default")
      (node (ref "U3") (pin "95") (pinfunction "PB8_95") (pintype "bidirectional"))
    )
    (net (code "123") (name "unconnected-(U3A-PB9-Pad96)") (class "Default")
      (node (ref "U3") (pin "96") (pinfunction "PB9_96") (pintype "bidirectional"))
    )
    (net (code "124") (name "unconnected-(U3A-PB15-Pad54)") (class "Default")
      (node (ref "U3") (pin "54") (pinfunction "PB15_54") (pintype "bidirectional"))
    )
    (net (code "125") (name "unconnected-(U3A-PC0-Pad15)") (class "Default")
      (node (ref "U3") (pin "15") (pinfunction "PC0_15") (pintype "bidirectional"))
    )
    (net (code "126") (name "unconnected-(U3A-PC2-Pad17)") (class "Default")
      (node (ref "U3") (pin "17") (pinfunction "PC2_17") (pintype "bidirectional"))
    )
    (net (code "127") (name "unconnected-(U3A-PC3-Pad18)") (class "Default")
      (node (ref "U3") (pin "18") (pinfunction "PC3_18") (pintype "bidirectional"))
    )
    (net (code "128") (name "unconnected-(U3A-PC8-Pad65)") (class "Default")
      (node (ref "U3") (pin "65") (pinfunction "PC8_65") (pintype "bidirectional"))
    )
    (net (code "129") (name "unconnected-(U3A-PC13-Pad7)") (class "Default")
      (node (ref "U3") (pin "7") (pinfunction "PC13_7") (pintype "bidirectional"))
    )
    (net (code "130") (name "unconnected-(U3A-PD0-Pad81)") (class "Default")
      (node (ref "U3") (pin "81") (pinfunction "PD0_81") (pintype "bidirectional"))
    )
    (net (code "131") (name "unconnected-(U3A-PD1-Pad82)") (class "Default")
      (node (ref "U3") (pin "82") (pinfunction "PD1_82") (pintype "bidirectional"))
    )
    (net (code "132") (name "unconnected-(U3A-PD3-Pad84)") (class "Default")
      (node (ref "U3") (pin "84") (pinfunction "PD3_84") (pintype "bidirectional"))
    )
    (net (code "133") (name "unconnected-(U3A-PD4-Pad85)") (class "Default")
      (node (ref "U3") (pin "85") (pinfunction "PD4_85") (pintype "bidirectional"))
    )
    (net (code "134") (name "unconnected-(U3A-PD5-Pad86)") (class "Default")
      (node (ref "U3") (pin "86") (pinfunction "PD5_86") (pintype "bidirectional"))
    )
    (net (code "135") (name "unconnected-(U3A-PD6-Pad87)") (class "Default")
      (node (ref "U3") (pin "87") (pinfunction "PD6_87") (pintype "bidirectional"))
    )
    (net (code "136") (name "unconnected-(U3A-PD7-Pad88)") (class "Default")
      (node (ref "U3") (pin "88") (pinfunction "PD7_88") (pintype "bidirectional"))
    )
    (net (code "137") (name "unconnected-(U3A-PD11-Pad58)") (class "Default")
      (node (ref "U3") (pin "58") (pinfunction "PD11_58") (pintype "bidirectional"))
    )
    (net (code "138") (name "unconnected-(U3A-PD13-Pad60)") (class "Default")
      (node (ref "U3") (pin "60") (pinfunction "PD13_60") (pintype "bidirectional"))
    )
    (net (code "139") (name "unconnected-(U3A-PD14-Pad61)") (class "Default")
      (node (ref "U3") (pin "61") (pinfunction "PD14_61") (pintype "bidirectional"))
    )
    (net (code "140") (name "unconnected-(U3A-PE2-Pad1)") (class "Default")
      (node (ref "U3") (pin "1") (pinfunction "PE2_1") (pintype "bidirectional"))
    )
    (net (code "141") (name "unconnected-(U3A-PE5-Pad4)") (class "Default")
      (node (ref "U3") (pin "4") (pinfunction "PE5_4") (pintype "bidirectional"))
    )
    (net (code "142") (name "unconnected-(U3A-PE6-Pad5)") (class "Default")
      (node (ref "U3") (pin "5") (pinfunction "PE6_5") (pintype "bidirectional"))
    )
    (net (code "143") (name "unconnected-(U3A-PE8-Pad39)") (class "Default")
      (node (ref "U3") (pin "39") (pinfunction "PE8_39") (pintype "bidirectional"))
    )
    (net (code "144") (name "unconnected-(U3A-PE9-Pad40)") (class "Default")
      (node (ref "U3") (pin "40") (pinfunction "PE9_40") (pintype "bidirectional"))
    )
    (net (code "145") (name "unconnected-(U3A-PE10-Pad41)") (class "Default")
      (node (ref "U3") (pin "41") (pinfunction "PE10_41") (pintype "bidirectional"))
    )
    (net (code "146") (name "unconnected-(U5-NC-Pad6)") (class "Default")
      (node (ref "U5") (pin "6") (pinfunction "NC_6") (pintype "power_in"))
    )
    (net (code "147") (name "unconnected-(U5-NC-Pad9)") (class "Default")
      (node (ref "U5") (pin "9") (pinfunction "NC_9") (pintype "power_in"))
    )
    (net (code "148") (name "unconnected-(U6-GPIO0-Pad23)") (class "Default")
      (node (ref "U6") (pin "23") (pinfunction "GPIO0_23") (pintype "power_in"))
    )
    (net (code "149") (name "unconnected-(U6-GPIO1-Pad11)") (class "Default")
      (node (ref "U6") (pin "11") (pinfunction "GPIO1_11") (pintype "power_in"))
    )
    (net (code "150") (name "unconnected-(U6-GPIO2-Pad13)") (class "Default")
      (node (ref "U6") (pin "13") (pinfunction "GPIO2_13") (pintype "power_in"))
    )
    (net (code "151") (name "unconnected-(U6-GPIO3-Pad16)") (class "Default")
      (node (ref "U6") (pin "16") (pinfunction "GPIO3_16") (pintype "power_in"))
    )
    (net (code "152") (name "unconnected-(U6-IO5-Pad20)") (class "Default")
      (node (ref "U6") (pin "20") (pinfunction "IO5_20") (pintype "power_in"))
    )
  )
)
